# Layer1.net
KiCad netlist of a schematic drawn in EAGLE
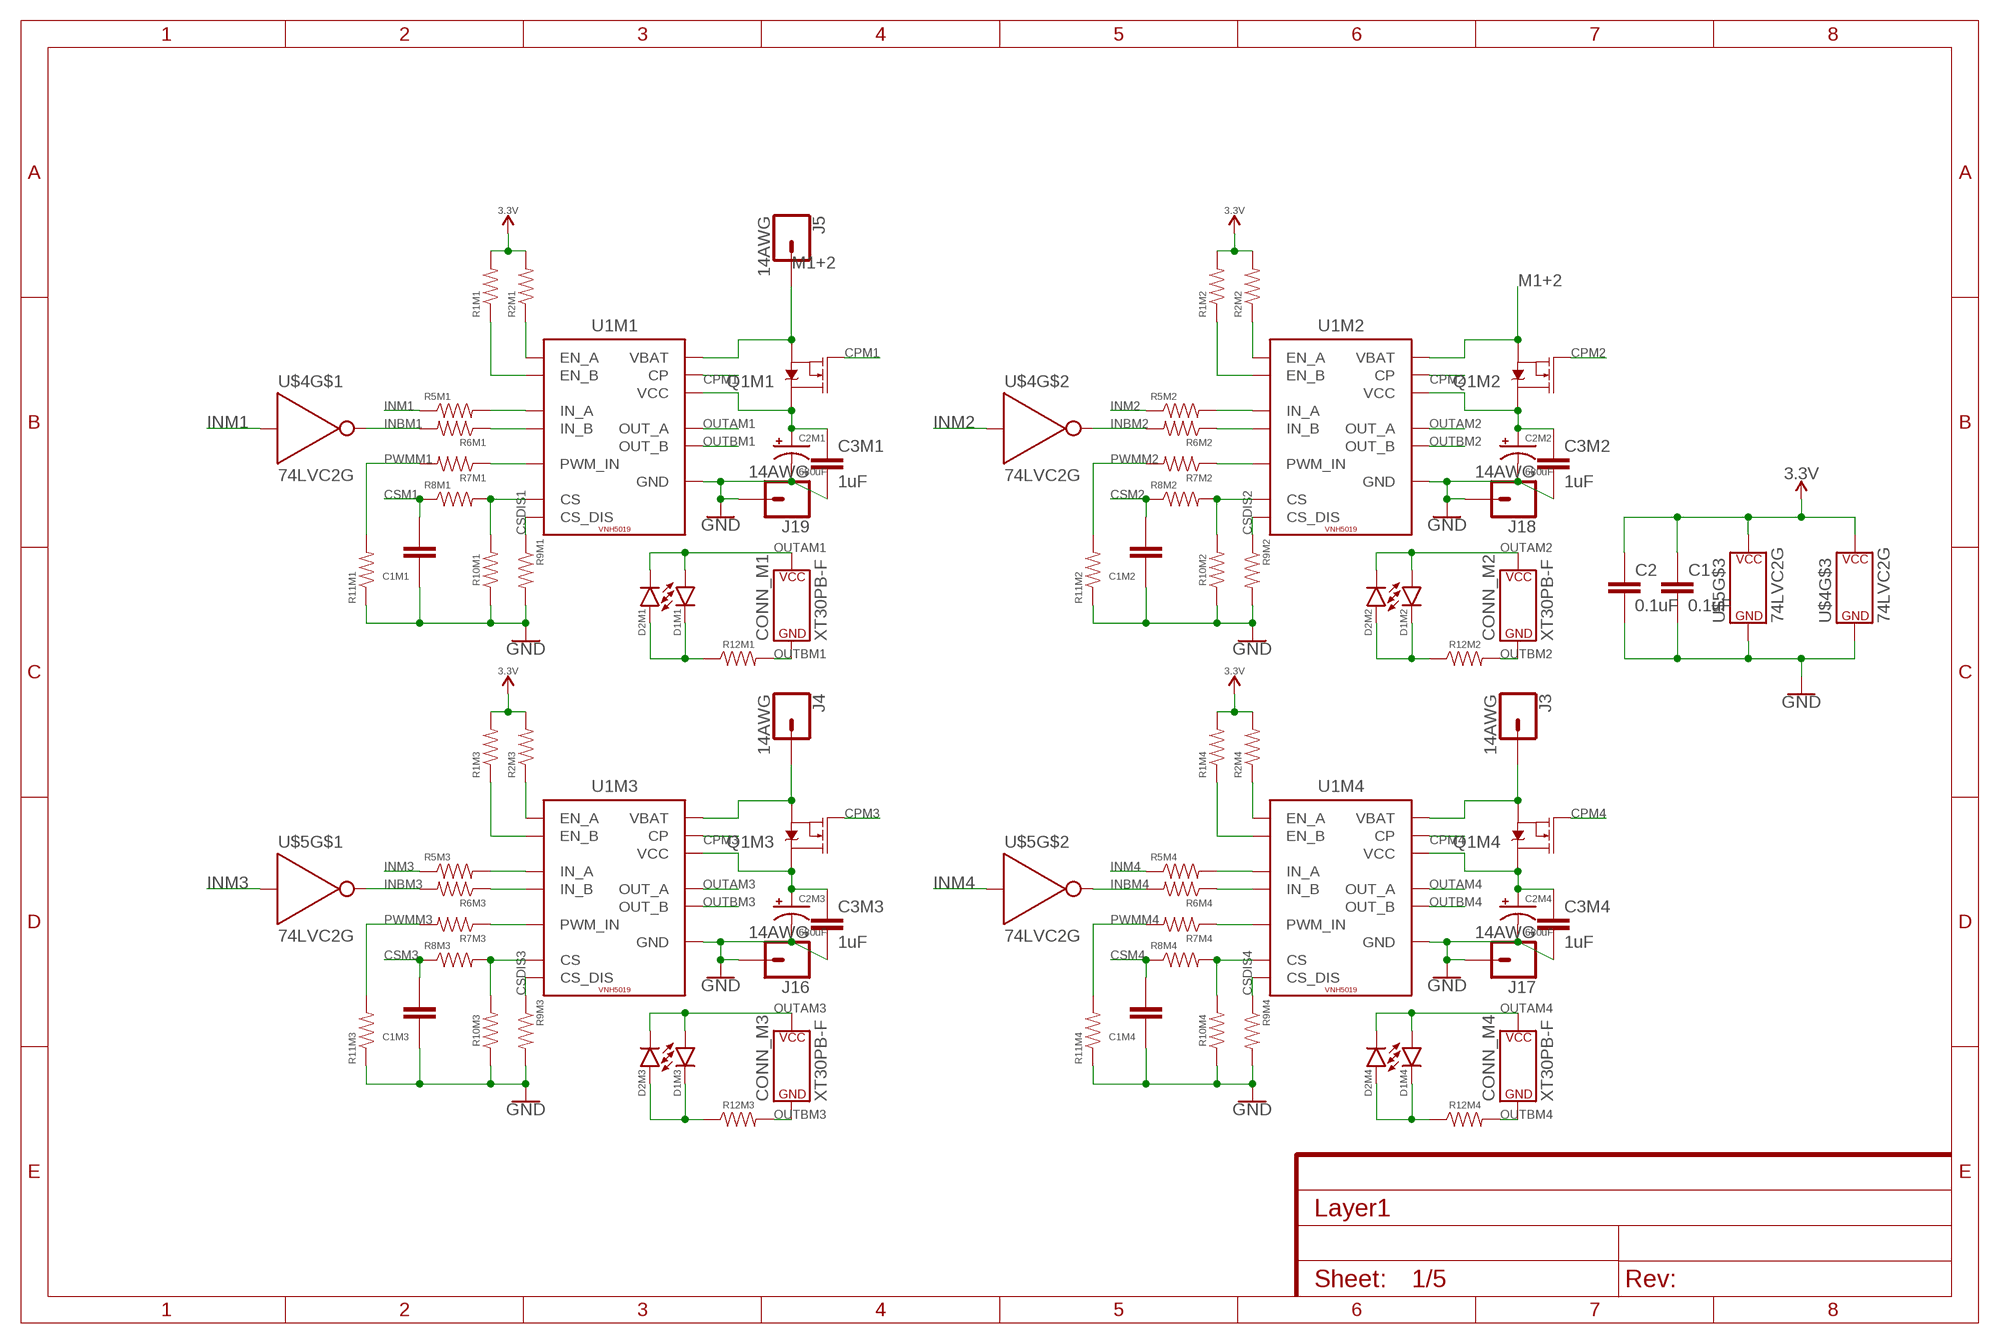
[diagram p0: schematic, sheet 1]
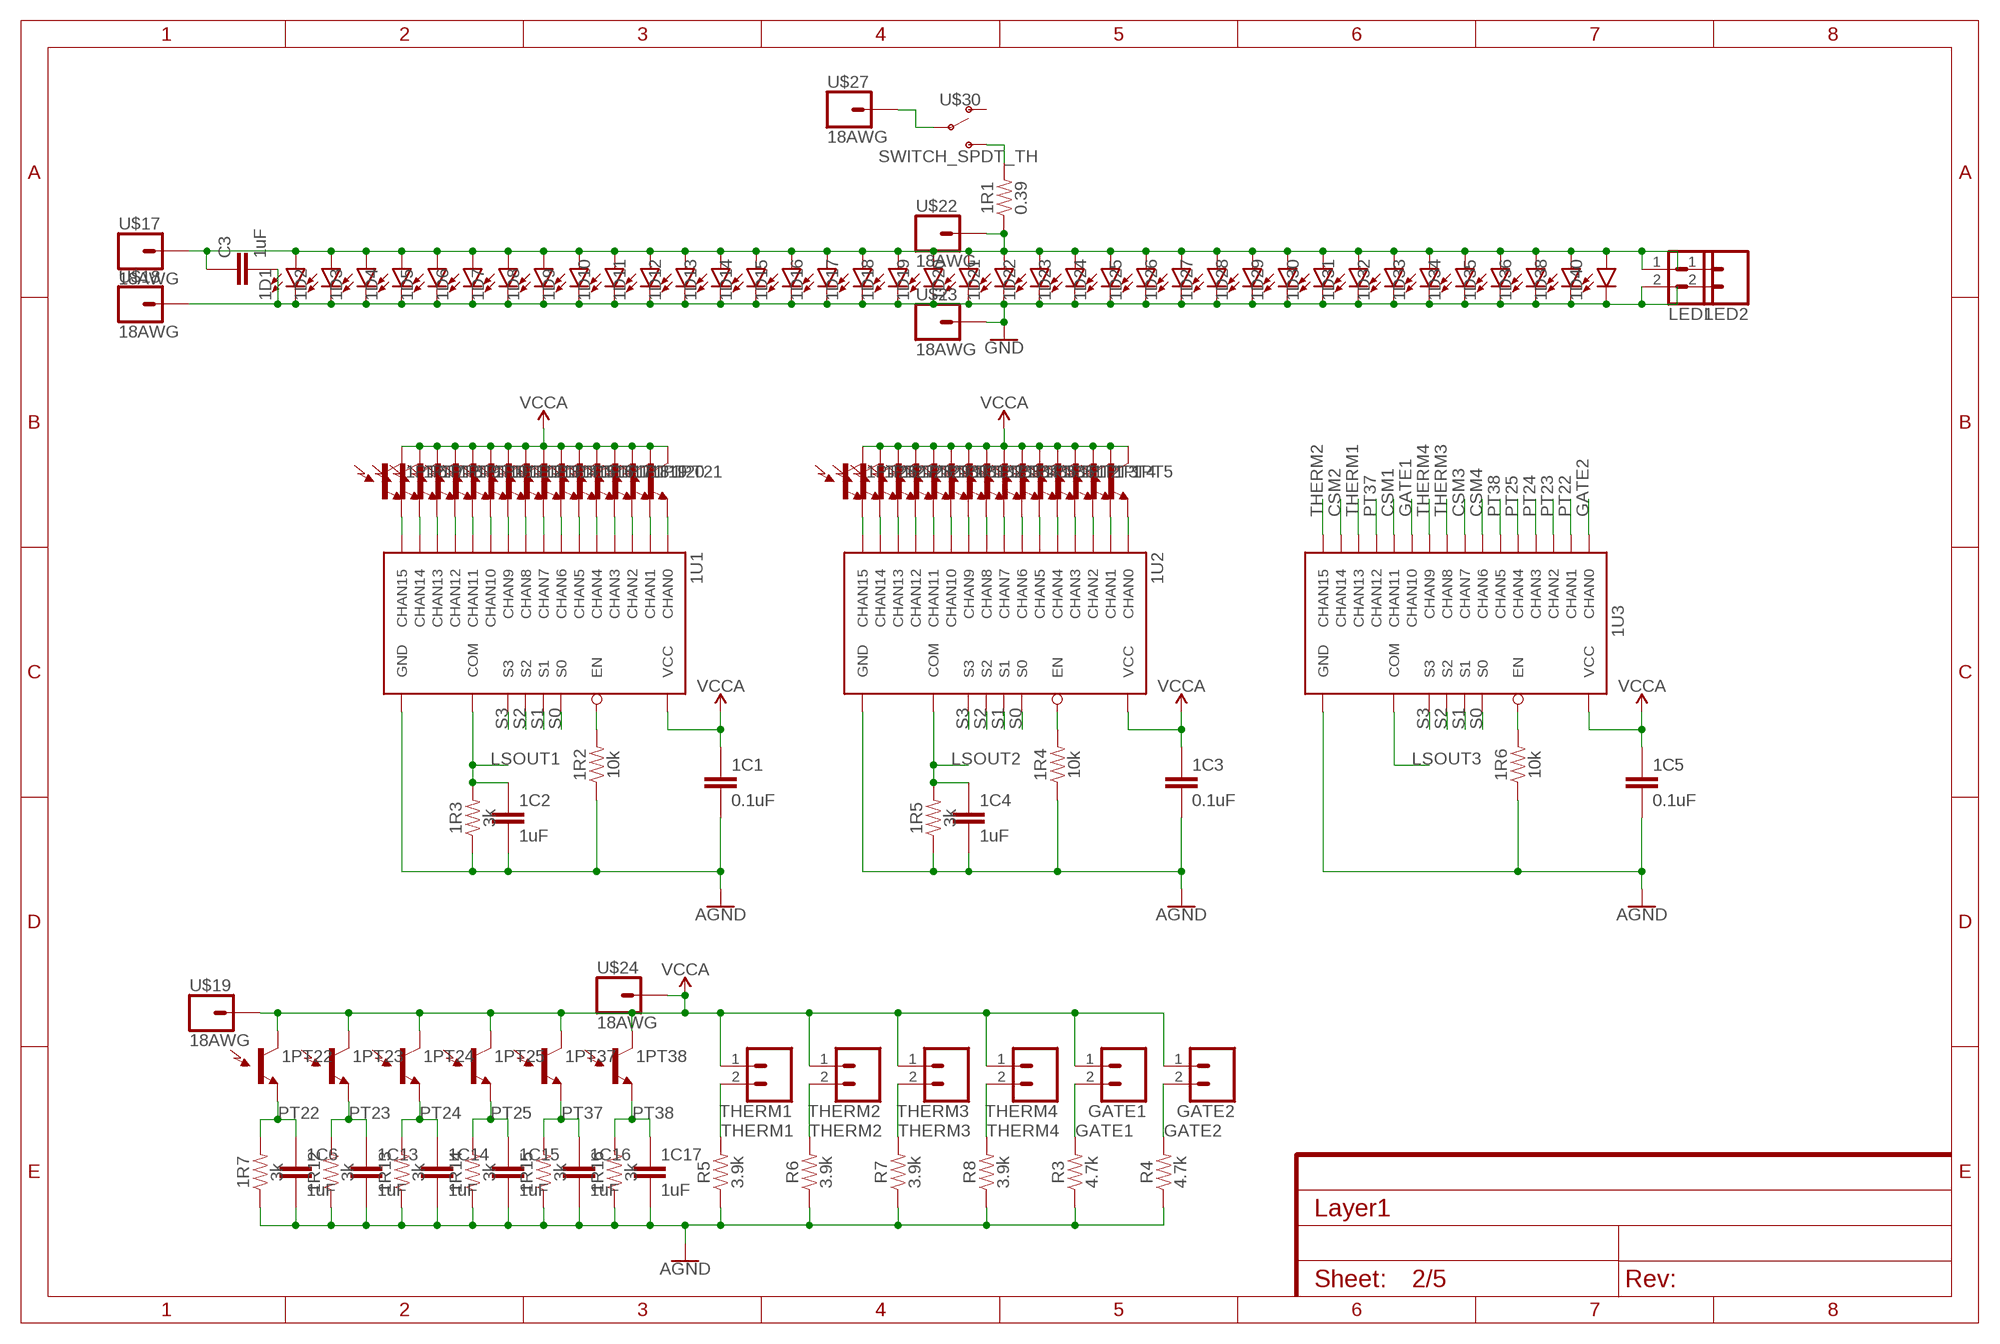
[diagram p1: schematic, sheet 2]
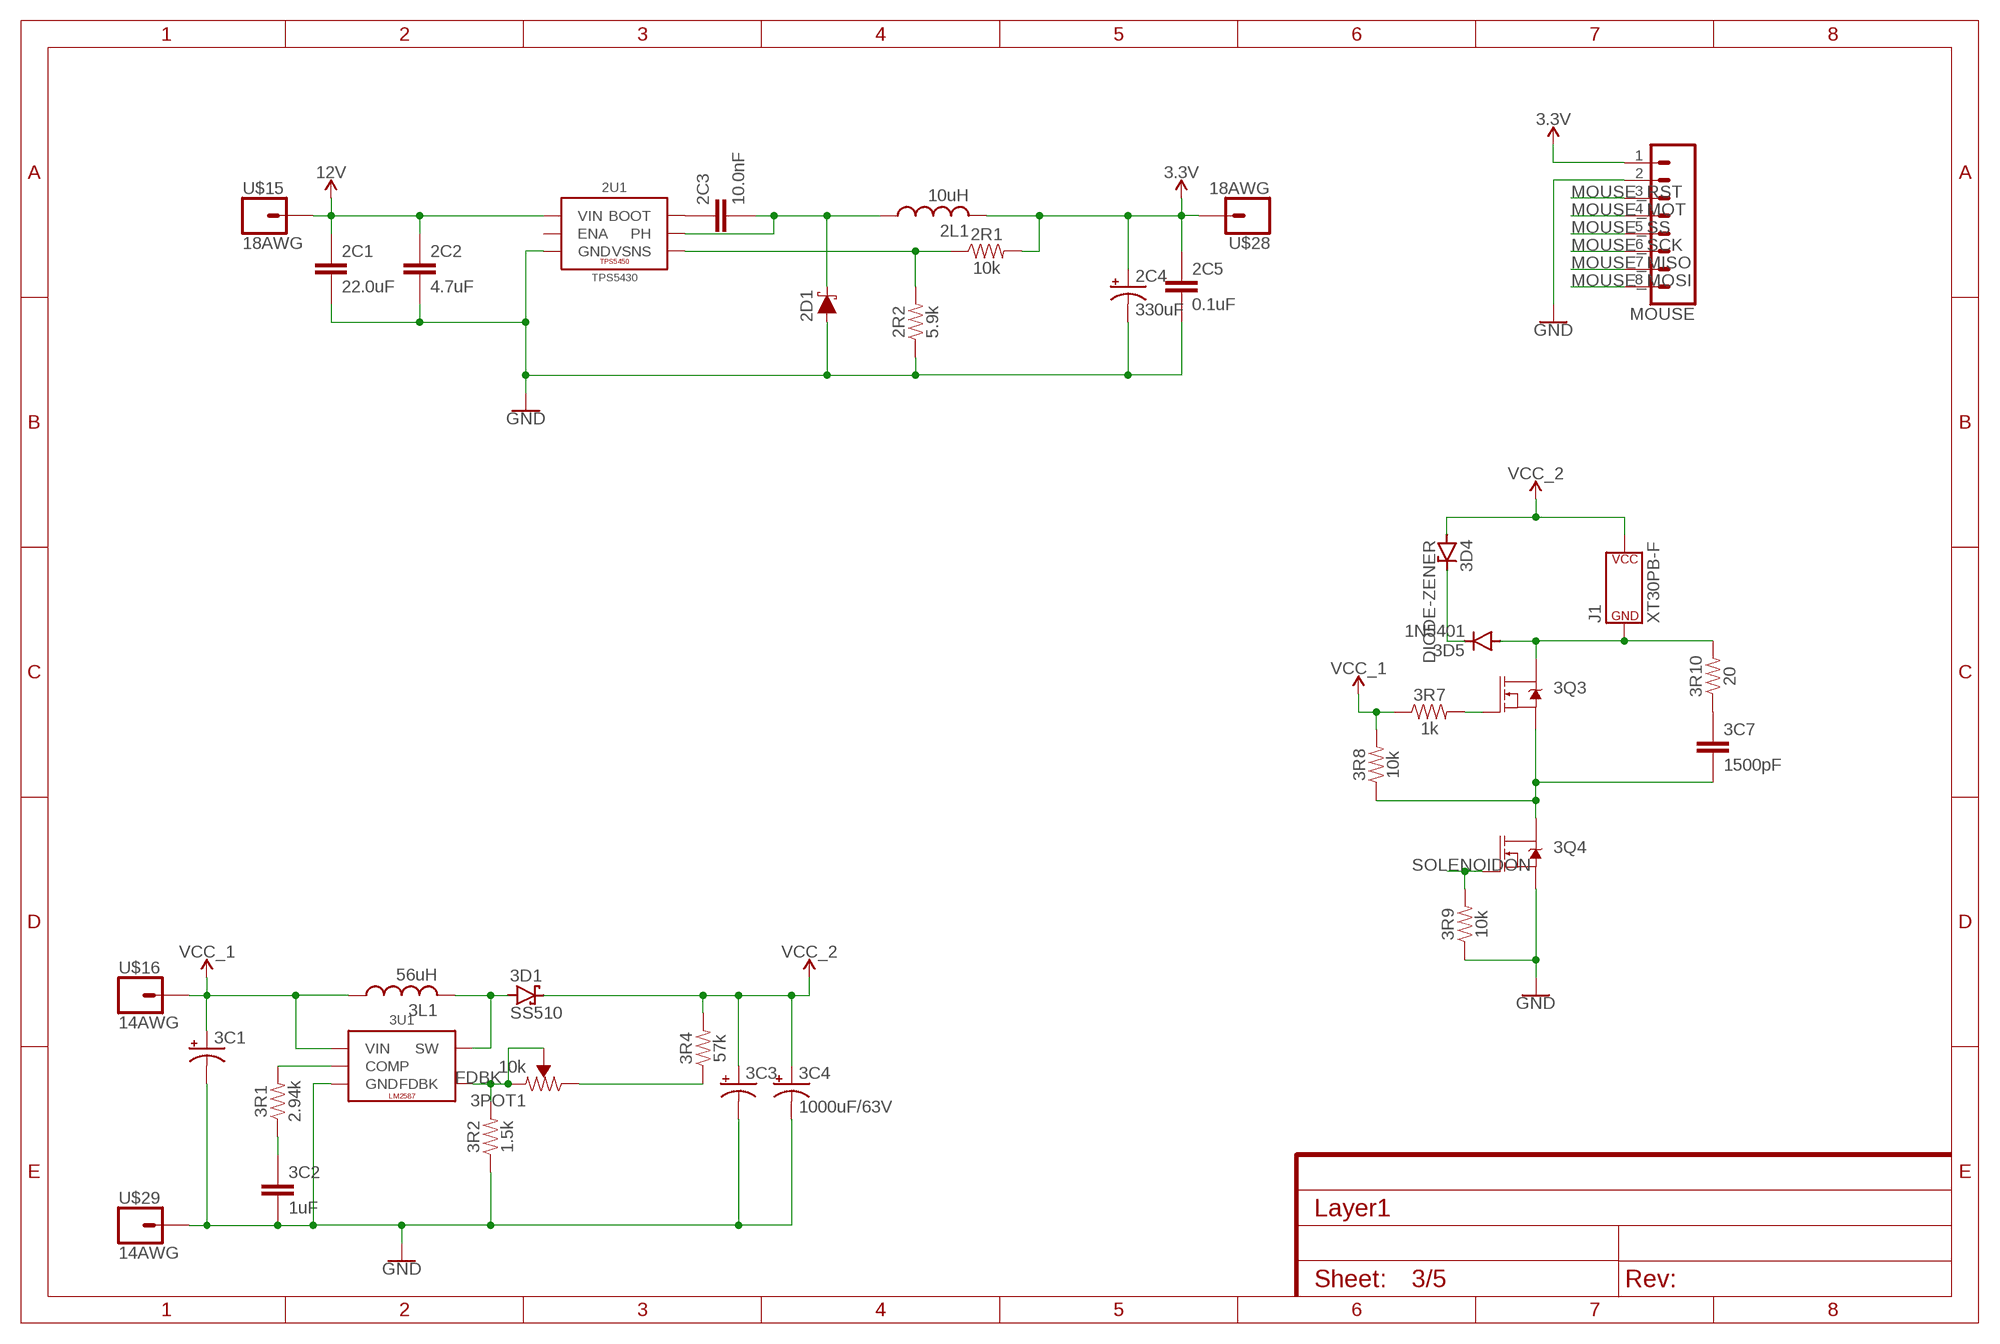
[diagram p2: schematic, sheet 3]
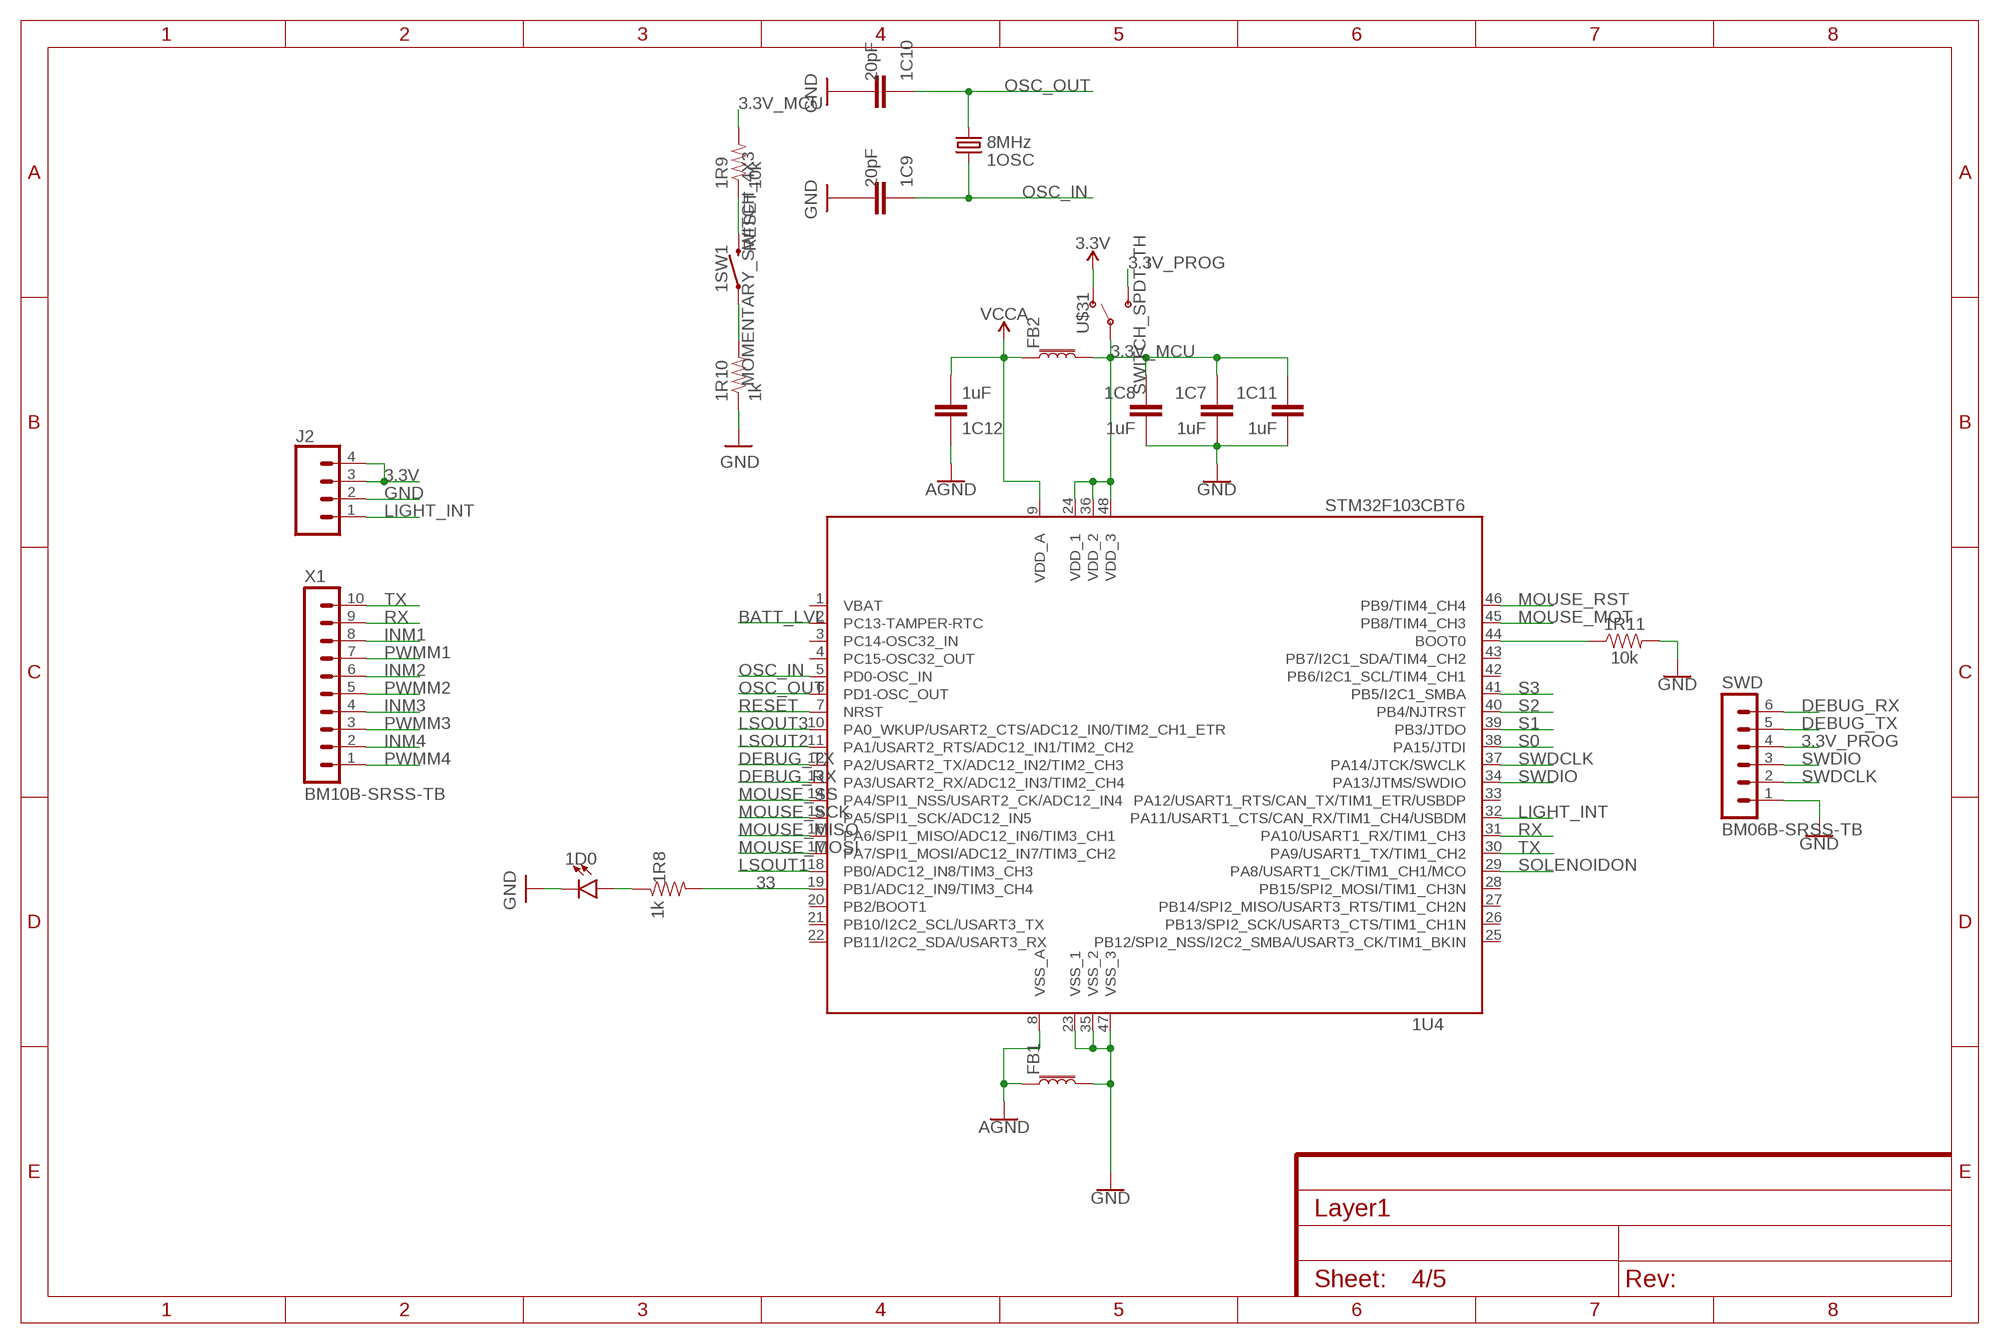
[diagram p3: schematic, sheet 4]
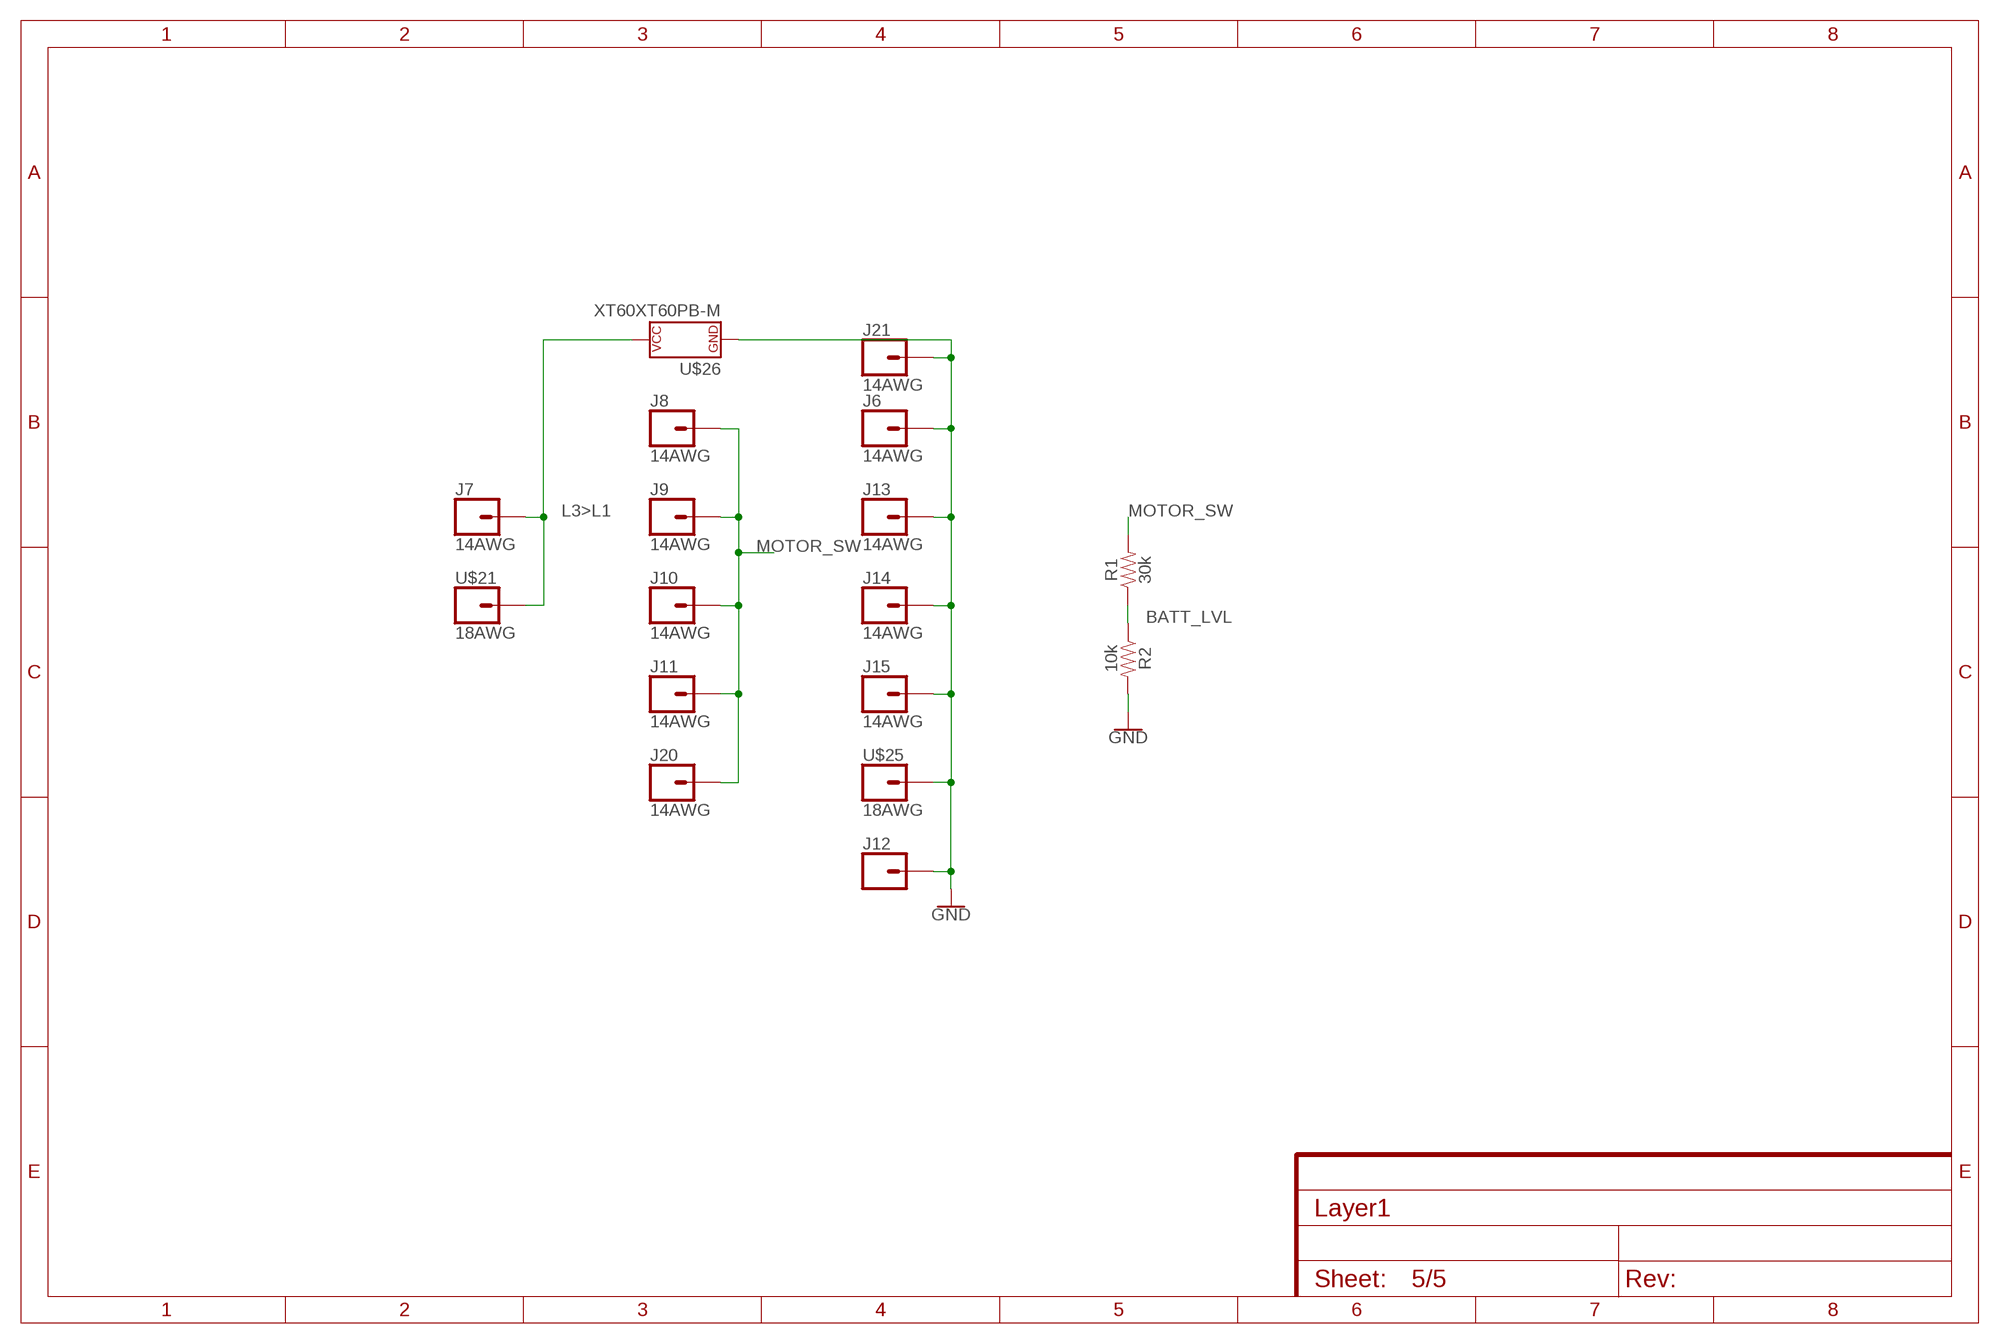
[diagram p4: schematic, sheet 5]

(export (version "E")
  (design (tool "Eeschema 10.0.6"))
  (components
    (comp (ref "J6")
      (value "14AWG")
      (footprint "eagle-import:14AWG")
      (libsource (lib "eagle-import") (part "14AWG"))
    )
    (comp (ref "J7")
      (value "14AWG")
      (footprint "eagle-import:14AWG")
      (libsource (lib "eagle-import") (part "14AWG"))
    )
    (comp (ref "J8")
      (value "14AWG")
      (footprint "eagle-import:14AWG")
      (libsource (lib "eagle-import") (part "14AWG"))
    )
    (comp (ref "J9")
      (value "14AWG")
      (footprint "eagle-import:14AWG")
      (libsource (lib "eagle-import") (part "14AWG"))
    )
    (comp (ref "J10")
      (value "14AWG")
      (footprint "eagle-import:14AWG")
      (libsource (lib "eagle-import") (part "14AWG"))
    )
    (comp (ref "J11")
      (value "14AWG")
      (footprint "eagle-import:14AWG")
      (libsource (lib "eagle-import") (part "14AWG"))
    )
    (comp (ref "J12")
      (value "CONN_01")
      (footprint "eagle-import:1X01")
      (libsource (lib "eagle-import") (part "CONN_01"))
    )
    (comp (ref "J13")
      (value "14AWG")
      (footprint "eagle-import:14AWG")
      (libsource (lib "eagle-import") (part "14AWG"))
    )
    (comp (ref "J14")
      (value "14AWG")
      (footprint "eagle-import:14AWG")
      (libsource (lib "eagle-import") (part "14AWG"))
    )
    (comp (ref "J15")
      (value "14AWG")
      (footprint "eagle-import:14AWG")
      (libsource (lib "eagle-import") (part "14AWG"))
    )
    (comp (ref "J20")
      (value "14AWG")
      (footprint "eagle-import:14AWG")
      (libsource (lib "eagle-import") (part "14AWG"))
    )
    (comp (ref "J21")
      (value "14AWG")
      (footprint "eagle-import:14AWG")
      (libsource (lib "eagle-import") (part "14AWG"))
    )
    (comp (ref "R1")
      (value "30k")
      (footprint "eagle-import:R0603")
      (libsource (lib "eagle-import") (part "RESISTOR0603"))
    )
    (comp (ref "R2")
      (value "10k")
      (footprint "eagle-import:R0603")
      (libsource (lib "eagle-import") (part "RESISTOR0603"))
    )
    (comp (ref "U$21")
      (value "18AWG")
      (footprint "eagle-import:18AWG")
      (libsource (lib "eagle-import") (part "18AWG"))
    )
    (comp (ref "U$25")
      (value "18AWG")
      (footprint "eagle-import:18AWG")
      (libsource (lib "eagle-import") (part "18AWG"))
    )
    (comp (ref "U$26")
      (value "XT60XT60PB-M")
      (footprint "eagle-import:XT60PB-M")
      (libsource (lib "eagle-import") (part "XT60XT60PB-M"))
    )
    (comp (ref "2C1")
      (value "22.0uF")
      (footprint "eagle-import:C1210")
      (libsource (lib "eagle-import") (part "CAPACITOR1210"))
    )
    (comp (ref "2C2")
      (value "4.7uF")
      (footprint "eagle-import:C0603")
      (libsource (lib "eagle-import") (part "CAPACITOR0603"))
    )
    (comp (ref "2C3")
      (value "10.0nF")
      (footprint "eagle-import:C0603")
      (libsource (lib "eagle-import") (part "CAPACITOR0603"))
    )
    (comp (ref "2C4")
      (value "330uF")
      (footprint "eagle-import:D_7343-31R")
      (libsource (lib "eagle-import") (part "CPOL-USD/7343-31R"))
    )
    (comp (ref "2C5")
      (value "0.1uF")
      (footprint "eagle-import:C0603")
      (libsource (lib "eagle-import") (part "CAPACITOR0603"))
    )
    (comp (ref "2D1")
      (value "SS54")
      (footprint "eagle-import:SMA-DIODE")
      (libsource (lib "eagle-import") (part "DIODE-SCHOTTKY"))
    )
    (comp (ref "2L1")
      (value "10uH")
      (footprint "eagle-import:SWPA8040")
      (libsource (lib "eagle-import") (part "INDUCTORSWPA8040"))
    )
    (comp (ref "2R1")
      (value "10k")
      (footprint "eagle-import:R0603")
      (libsource (lib "eagle-import") (part "RESISTOR0603"))
    )
    (comp (ref "2R2")
      (value "5.9k")
      (footprint "eagle-import:R0603")
      (libsource (lib "eagle-import") (part "RESISTOR0603"))
    )
    (comp (ref "2U1")
      (value "TPS5430")
      (footprint "eagle-import:POWERPAD-SOIC-8")
      (libsource (lib "eagle-import") (part "TPS5450"))
    )
    (comp (ref "3C1")
      (value "100uF")
      (footprint "eagle-import:PANASONIC_D")
      (libsource (lib "eagle-import") (part "CPOL-USD"))
    )
    (comp (ref "3C2")
      (value "1uF")
      (footprint "eagle-import:C0603")
      (libsource (lib "eagle-import") (part "CAPACITOR0603"))
    )
    (comp (ref "3C3")
      (value "CAPACITOR_POL_10X10.5MM")
      (footprint "eagle-import:10X10.5_CAP")
      (libsource (lib "eagle-import") (part "CAPACITOR_POL_10X10.5MM"))
    )
    (comp (ref "3C4")
      (value "1000uF/63V")
      (footprint "eagle-import:1000UF-CAP")
      (libsource (lib "eagle-import") (part "1000UF-CAP"))
    )
    (comp (ref "3C7")
      (value "1500pF")
      (footprint "eagle-import:C0603")
      (libsource (lib "eagle-import") (part "CAPACITOR0603"))
    )
    (comp (ref "3D1")
      (value "SS510")
      (footprint "eagle-import:SMB")
      (libsource (lib "eagle-import") (part "SCHOTTKY-DIODESMD"))
    )
    (comp (ref "3D4")
      (value "DIODE-ZENER")
      (footprint "eagle-import:DO41Z10")
      (libsource (lib "eagle-import") (part "DIODE-ZENER"))
    )
    (comp (ref "3D5")
      (value "1N5401")
      (footprint "eagle-import:DO201-15")
      (libsource (lib "eagle-import") (part "1N5400"))
    )
    (comp (ref "3L1")
      (value "56uH")
      (footprint "eagle-import:CDRH127")
      (libsource (lib "eagle-import") (part "INDUCTORCDRH127"))
    )
    (comp (ref "3POT1")
      (value "10k")
      (footprint "eagle-import:3296-TRIMPOT")
      (libsource (lib "eagle-import") (part "3296-TRIMPOT"))
    )
    (comp (ref "3Q3")
      (value "STP75NF75")
      (footprint "eagle-import:TO220V")
      (libsource (lib "eagle-import") (part "MOSFET-NCH-TO220V"))
    )
    (comp (ref "3Q4")
      (value "AO3400")
      (footprint "eagle-import:SOT23-3")
      (libsource (lib "eagle-import") (part "MOSFET-NCH-SOT23-3"))
    )
    (comp (ref "3R1")
      (value "2.94k")
      (footprint "eagle-import:R0603")
      (libsource (lib "eagle-import") (part "RESISTOR0603"))
    )
    (comp (ref "3R2")
      (value "1.5k")
      (footprint "eagle-import:R0603")
      (libsource (lib "eagle-import") (part "RESISTOR0603"))
    )
    (comp (ref "3R4")
      (value "57k")
      (footprint "eagle-import:R0603")
      (libsource (lib "eagle-import") (part "RESISTOR0603"))
    )
    (comp (ref "3R7")
      (value "1k")
      (footprint "eagle-import:R0603")
      (libsource (lib "eagle-import") (part "RESISTOR0603"))
    )
    (comp (ref "3R8")
      (value "10k")
      (footprint "eagle-import:R0603")
      (libsource (lib "eagle-import") (part "RESISTOR0603"))
    )
    (comp (ref "3R9")
      (value "10k")
      (footprint "eagle-import:R0603")
      (libsource (lib "eagle-import") (part "RESISTOR0603"))
    )
    (comp (ref "3R10")
      (value "20")
      (footprint "eagle-import:R0603")
      (libsource (lib "eagle-import") (part "RESISTOR0603"))
    )
    (comp (ref "3U1")
      (value "LM2587")
      (footprint "eagle-import:TO-263")
      (libsource (lib "eagle-import") (part "LM2587"))
    )
    (comp (ref "J1")
      (value "XT30PB-F")
      (footprint "eagle-import:XT30PB-F")
      (libsource (lib "eagle-import") (part "XT30PB-F"))
    )
    (comp (ref "MOUSE")
      (value "CONN_08LOCK")
      (footprint "eagle-import:1X08_LOCK")
      (libsource (lib "eagle-import") (part "CONN_08LOCK"))
    )
    (comp (ref "U$15")
      (value "18AWG")
      (footprint "eagle-import:18AWG")
      (libsource (lib "eagle-import") (part "18AWG"))
    )
    (comp (ref "U$16")
      (value "14AWG")
      (footprint "eagle-import:14AWG")
      (libsource (lib "eagle-import") (part "14AWG"))
    )
    (comp (ref "U$28")
      (value "18AWG")
      (footprint "eagle-import:18AWG")
      (libsource (lib "eagle-import") (part "18AWG"))
    )
    (comp (ref "U$29")
      (value "14AWG")
      (footprint "eagle-import:14AWG")
      (libsource (lib "eagle-import") (part "14AWG"))
    )
    (comp (ref "1C1")
      (value "0.1uF")
      (footprint "eagle-import:C0603")
      (libsource (lib "eagle-import") (part "CAPACITOR0603"))
    )
    (comp (ref "1C2")
      (value "1uF")
      (footprint "eagle-import:C0603")
      (libsource (lib "eagle-import") (part "CAPACITOR0603"))
    )
    (comp (ref "1C3")
      (value "0.1uF")
      (footprint "eagle-import:C0603")
      (libsource (lib "eagle-import") (part "CAPACITOR0603"))
    )
    (comp (ref "1C4")
      (value "1uF")
      (footprint "eagle-import:C0603")
      (libsource (lib "eagle-import") (part "CAPACITOR0603"))
    )
    (comp (ref "1C5")
      (value "0.1uF")
      (footprint "eagle-import:C0603")
      (libsource (lib "eagle-import") (part "CAPACITOR0603"))
    )
    (comp (ref "1C6")
      (value "1uF")
      (footprint "eagle-import:C0603")
      (libsource (lib "eagle-import") (part "CAPACITOR0603"))
    )
    (comp (ref "1C13")
      (value "1uF")
      (footprint "eagle-import:C0603")
      (libsource (lib "eagle-import") (part "CAPACITOR0603"))
    )
    (comp (ref "1C14")
      (value "1uF")
      (footprint "eagle-import:C0603")
      (libsource (lib "eagle-import") (part "CAPACITOR0603"))
    )
    (comp (ref "1C15")
      (value "1uF")
      (footprint "eagle-import:C0603")
      (libsource (lib "eagle-import") (part "CAPACITOR0603"))
    )
    (comp (ref "1C16")
      (value "1uF")
      (footprint "eagle-import:C0603")
      (libsource (lib "eagle-import") (part "CAPACITOR0603"))
    )
    (comp (ref "1C17")
      (value "1uF")
      (footprint "eagle-import:C0603")
      (libsource (lib "eagle-import") (part "CAPACITOR0603"))
    )
    (comp (ref "1D1")
      (value "3528LED")
      (footprint "eagle-import:3528")
      (libsource (lib "eagle-import") (part "3528LED"))
    )
    (comp (ref "1D2")
      (value "3528LED")
      (footprint "eagle-import:3528")
      (libsource (lib "eagle-import") (part "3528LED"))
    )
    (comp (ref "1D3")
      (value "3528LED")
      (footprint "eagle-import:3528")
      (libsource (lib "eagle-import") (part "3528LED"))
    )
    (comp (ref "1D4")
      (value "3528LED")
      (footprint "eagle-import:3528")
      (libsource (lib "eagle-import") (part "3528LED"))
    )
    (comp (ref "1D5")
      (value "3528LED")
      (footprint "eagle-import:3528")
      (libsource (lib "eagle-import") (part "3528LED"))
    )
    (comp (ref "1D6")
      (value "3528LED")
      (footprint "eagle-import:3528")
      (libsource (lib "eagle-import") (part "3528LED"))
    )
    (comp (ref "1D7")
      (value "3528LED")
      (footprint "eagle-import:3528")
      (libsource (lib "eagle-import") (part "3528LED"))
    )
    (comp (ref "1D8")
      (value "3528LED")
      (footprint "eagle-import:3528")
      (libsource (lib "eagle-import") (part "3528LED"))
    )
    (comp (ref "1D9")
      (value "3528LED")
      (footprint "eagle-import:3528")
      (libsource (lib "eagle-import") (part "3528LED"))
    )
    (comp (ref "1D10")
      (value "3528LED")
      (footprint "eagle-import:3528")
      (libsource (lib "eagle-import") (part "3528LED"))
    )
    (comp (ref "1D11")
      (value "3528LED")
      (footprint "eagle-import:3528")
      (libsource (lib "eagle-import") (part "3528LED"))
    )
    (comp (ref "1D12")
      (value "3528LED")
      (footprint "eagle-import:3528")
      (libsource (lib "eagle-import") (part "3528LED"))
    )
    (comp (ref "1D13")
      (value "3528LED")
      (footprint "eagle-import:3528")
      (libsource (lib "eagle-import") (part "3528LED"))
    )
    (comp (ref "1D14")
      (value "3528LED")
      (footprint "eagle-import:3528")
      (libsource (lib "eagle-import") (part "3528LED"))
    )
    (comp (ref "1D15")
      (value "3528LED")
      (footprint "eagle-import:3528")
      (libsource (lib "eagle-import") (part "3528LED"))
    )
    (comp (ref "1D16")
      (value "3528LED")
      (footprint "eagle-import:3528")
      (libsource (lib "eagle-import") (part "3528LED"))
    )
    (comp (ref "1D17")
      (value "3528LED")
      (footprint "eagle-import:3528")
      (libsource (lib "eagle-import") (part "3528LED"))
    )
    (comp (ref "1D18")
      (value "3528LED")
      (footprint "eagle-import:3528")
      (libsource (lib "eagle-import") (part "3528LED"))
    )
    (comp (ref "1D19")
      (value "3528LED")
      (footprint "eagle-import:3528")
      (libsource (lib "eagle-import") (part "3528LED"))
    )
    (comp (ref "1D20")
      (value "3528LED")
      (footprint "eagle-import:3528")
      (libsource (lib "eagle-import") (part "3528LED"))
    )
    (comp (ref "1D21")
      (value "3528LED")
      (footprint "eagle-import:3528")
      (libsource (lib "eagle-import") (part "3528LED"))
    )
    (comp (ref "1D22")
      (value "3528LED")
      (footprint "eagle-import:3528")
      (libsource (lib "eagle-import") (part "3528LED"))
    )
    (comp (ref "1D23")
      (value "3528LED")
      (footprint "eagle-import:3528")
      (libsource (lib "eagle-import") (part "3528LED"))
    )
    (comp (ref "1D24")
      (value "3528LED")
      (footprint "eagle-import:3528")
      (libsource (lib "eagle-import") (part "3528LED"))
    )
    (comp (ref "1D25")
      (value "3528LED")
      (footprint "eagle-import:3528")
      (libsource (lib "eagle-import") (part "3528LED"))
    )
    (comp (ref "1D26")
      (value "3528LED")
      (footprint "eagle-import:3528")
      (libsource (lib "eagle-import") (part "3528LED"))
    )
    (comp (ref "1D27")
      (value "3528LED")
      (footprint "eagle-import:3528")
      (libsource (lib "eagle-import") (part "3528LED"))
    )
    (comp (ref "1D28")
      (value "3528LED")
      (footprint "eagle-import:3528")
      (libsource (lib "eagle-import") (part "3528LED"))
    )
    (comp (ref "1D29")
      (value "3528LED")
      (footprint "eagle-import:3528")
      (libsource (lib "eagle-import") (part "3528LED"))
    )
    (comp (ref "1D30")
      (value "3528LED")
      (footprint "eagle-import:3528")
      (libsource (lib "eagle-import") (part "3528LED"))
    )
    (comp (ref "1D31")
      (value "3528LED")
      (footprint "eagle-import:3528")
      (libsource (lib "eagle-import") (part "3528LED"))
    )
    (comp (ref "1D32")
      (value "3528LED")
      (footprint "eagle-import:3528")
      (libsource (lib "eagle-import") (part "3528LED"))
    )
    (comp (ref "1D33")
      (value "3528LED")
      (footprint "eagle-import:3528")
      (libsource (lib "eagle-import") (part "3528LED"))
    )
    (comp (ref "1D34")
      (value "3528LED")
      (footprint "eagle-import:3528")
      (libsource (lib "eagle-import") (part "3528LED"))
    )
    (comp (ref "1D35")
      (value "3528LED")
      (footprint "eagle-import:3528")
      (libsource (lib "eagle-import") (part "3528LED"))
    )
    (comp (ref "1D36")
      (value "3528LED")
      (footprint "eagle-import:3528")
      (libsource (lib "eagle-import") (part "3528LED"))
    )
    (comp (ref "1D38")
      (value "3528LED")
      (footprint "eagle-import:3528")
      (libsource (lib "eagle-import") (part "3528LED"))
    )
    (comp (ref "1D40")
      (value "3528LED")
      (footprint "eagle-import:3528")
      (libsource (lib "eagle-import") (part "3528LED"))
    )
    (comp (ref "1PT1")
      (value "LIGHT_SENSOR_ALS")
      (footprint "eagle-import:ALS-PT19")
      (libsource (lib "eagle-import") (part "LIGHT_SENSOR_ALS"))
    )
    (comp (ref "1PT2")
      (value "LIGHT_SENSOR_ALS")
      (footprint "eagle-import:ALS-PT19")
      (libsource (lib "eagle-import") (part "LIGHT_SENSOR_ALS"))
    )
    (comp (ref "1PT3")
      (value "LIGHT_SENSOR_ALS")
      (footprint "eagle-import:ALS-PT19")
      (libsource (lib "eagle-import") (part "LIGHT_SENSOR_ALS"))
    )
    (comp (ref "1PT4")
      (value "LIGHT_SENSOR_ALS")
      (footprint "eagle-import:ALS-PT19")
      (libsource (lib "eagle-import") (part "LIGHT_SENSOR_ALS"))
    )
    (comp (ref "1PT5")
      (value "LIGHT_SENSOR_ALS")
      (footprint "eagle-import:ALS-PT19")
      (libsource (lib "eagle-import") (part "LIGHT_SENSOR_ALS"))
    )
    (comp (ref "1PT6")
      (value "LIGHT_SENSOR_ALS")
      (footprint "eagle-import:ALS-PT19")
      (libsource (lib "eagle-import") (part "LIGHT_SENSOR_ALS"))
    )
    (comp (ref "1PT7")
      (value "LIGHT_SENSOR_ALS")
      (footprint "eagle-import:ALS-PT19")
      (libsource (lib "eagle-import") (part "LIGHT_SENSOR_ALS"))
    )
    (comp (ref "1PT8")
      (value "LIGHT_SENSOR_ALS")
      (footprint "eagle-import:ALS-PT19")
      (libsource (lib "eagle-import") (part "LIGHT_SENSOR_ALS"))
    )
    (comp (ref "1PT9")
      (value "LIGHT_SENSOR_ALS")
      (footprint "eagle-import:ALS-PT19")
      (libsource (lib "eagle-import") (part "LIGHT_SENSOR_ALS"))
    )
    (comp (ref "1PT10")
      (value "LIGHT_SENSOR_ALS")
      (footprint "eagle-import:ALS-PT19")
      (libsource (lib "eagle-import") (part "LIGHT_SENSOR_ALS"))
    )
    (comp (ref "1PT11")
      (value "LIGHT_SENSOR_ALS")
      (footprint "eagle-import:ALS-PT19")
      (libsource (lib "eagle-import") (part "LIGHT_SENSOR_ALS"))
    )
    (comp (ref "1PT12")
      (value "LIGHT_SENSOR_ALS")
      (footprint "eagle-import:ALS-PT19")
      (libsource (lib "eagle-import") (part "LIGHT_SENSOR_ALS"))
    )
    (comp (ref "1PT13")
      (value "LIGHT_SENSOR_ALS")
      (footprint "eagle-import:ALS-PT19")
      (libsource (lib "eagle-import") (part "LIGHT_SENSOR_ALS"))
    )
    (comp (ref "1PT14")
      (value "LIGHT_SENSOR_ALS")
      (footprint "eagle-import:ALS-PT19")
      (libsource (lib "eagle-import") (part "LIGHT_SENSOR_ALS"))
    )
    (comp (ref "1PT15")
      (value "LIGHT_SENSOR_ALS")
      (footprint "eagle-import:ALS-PT19")
      (libsource (lib "eagle-import") (part "LIGHT_SENSOR_ALS"))
    )
    (comp (ref "1PT16")
      (value "LIGHT_SENSOR_ALS")
      (footprint "eagle-import:ALS-PT19")
      (libsource (lib "eagle-import") (part "LIGHT_SENSOR_ALS"))
    )
    (comp (ref "1PT17")
      (value "LIGHT_SENSOR_ALS")
      (footprint "eagle-import:ALS-PT19")
      (libsource (lib "eagle-import") (part "LIGHT_SENSOR_ALS"))
    )
    (comp (ref "1PT18")
      (value "LIGHT_SENSOR_ALS")
      (footprint "eagle-import:ALS-PT19")
      (libsource (lib "eagle-import") (part "LIGHT_SENSOR_ALS"))
    )
    (comp (ref "1PT19")
      (value "LIGHT_SENSOR_ALS")
      (footprint "eagle-import:ALS-PT19")
      (libsource (lib "eagle-import") (part "LIGHT_SENSOR_ALS"))
    )
    (comp (ref "1PT20")
      (value "LIGHT_SENSOR_ALS")
      (footprint "eagle-import:ALS-PT19")
      (libsource (lib "eagle-import") (part "LIGHT_SENSOR_ALS"))
    )
    (comp (ref "1PT21")
      (value "LIGHT_SENSOR_ALS")
      (footprint "eagle-import:ALS-PT19")
      (libsource (lib "eagle-import") (part "LIGHT_SENSOR_ALS"))
    )
    (comp (ref "1PT22")
      (value "LIGHT_SENSOR_ALS")
      (footprint "eagle-import:ALS-PT19")
      (libsource (lib "eagle-import") (part "LIGHT_SENSOR_ALS"))
    )
    (comp (ref "1PT23")
      (value "LIGHT_SENSOR_ALS")
      (footprint "eagle-import:ALS-PT19")
      (libsource (lib "eagle-import") (part "LIGHT_SENSOR_ALS"))
    )
    (comp (ref "1PT24")
      (value "LIGHT_SENSOR_ALS")
      (footprint "eagle-import:ALS-PT19")
      (libsource (lib "eagle-import") (part "LIGHT_SENSOR_ALS"))
    )
    (comp (ref "1PT25")
      (value "LIGHT_SENSOR_ALS")
      (footprint "eagle-import:ALS-PT19")
      (libsource (lib "eagle-import") (part "LIGHT_SENSOR_ALS"))
    )
    (comp (ref "1PT26")
      (value "LIGHT_SENSOR_ALS")
      (footprint "eagle-import:ALS-PT19")
      (libsource (lib "eagle-import") (part "LIGHT_SENSOR_ALS"))
    )
    (comp (ref "1PT27")
      (value "LIGHT_SENSOR_ALS")
      (footprint "eagle-import:ALS-PT19")
      (libsource (lib "eagle-import") (part "LIGHT_SENSOR_ALS"))
    )
    (comp (ref "1PT28")
      (value "LIGHT_SENSOR_ALS")
      (footprint "eagle-import:ALS-PT19")
      (libsource (lib "eagle-import") (part "LIGHT_SENSOR_ALS"))
    )
    (comp (ref "1PT29")
      (value "LIGHT_SENSOR_ALS")
      (footprint "eagle-import:ALS-PT19")
      (libsource (lib "eagle-import") (part "LIGHT_SENSOR_ALS"))
    )
    (comp (ref "1PT30")
      (value "LIGHT_SENSOR_ALS")
      (footprint "eagle-import:ALS-PT19")
      (libsource (lib "eagle-import") (part "LIGHT_SENSOR_ALS"))
    )
    (comp (ref "1PT31")
      (value "LIGHT_SENSOR_ALS")
      (footprint "eagle-import:ALS-PT19")
      (libsource (lib "eagle-import") (part "LIGHT_SENSOR_ALS"))
    )
    (comp (ref "1PT32")
      (value "LIGHT_SENSOR_ALS")
      (footprint "eagle-import:ALS-PT19")
      (libsource (lib "eagle-import") (part "LIGHT_SENSOR_ALS"))
    )
    (comp (ref "1PT33")
      (value "LIGHT_SENSOR_ALS")
      (footprint "eagle-import:ALS-PT19")
      (libsource (lib "eagle-import") (part "LIGHT_SENSOR_ALS"))
    )
    (comp (ref "1PT34")
      (value "LIGHT_SENSOR_ALS")
      (footprint "eagle-import:ALS-PT19")
      (libsource (lib "eagle-import") (part "LIGHT_SENSOR_ALS"))
    )
    (comp (ref "1PT35")
      (value "LIGHT_SENSOR_ALS")
      (footprint "eagle-import:ALS-PT19")
      (libsource (lib "eagle-import") (part "LIGHT_SENSOR_ALS"))
    )
    (comp (ref "1PT36")
      (value "LIGHT_SENSOR_ALS")
      (footprint "eagle-import:ALS-PT19")
      (libsource (lib "eagle-import") (part "LIGHT_SENSOR_ALS"))
    )
    (comp (ref "1PT37")
      (value "LIGHT_SENSOR_ALS")
      (footprint "eagle-import:ALS-PT19")
      (libsource (lib "eagle-import") (part "LIGHT_SENSOR_ALS"))
    )
    (comp (ref "1PT38")
      (value "LIGHT_SENSOR_ALS")
      (footprint "eagle-import:ALS-PT19")
      (libsource (lib "eagle-import") (part "LIGHT_SENSOR_ALS"))
    )
    (comp (ref "1R1")
      (value "0.39")
      (footprint "eagle-import:R0603")
      (libsource (lib "eagle-import") (part "RESISTOR0603"))
    )
    (comp (ref "1R2")
      (value "10k")
      (footprint "eagle-import:R0603")
      (libsource (lib "eagle-import") (part "RESISTOR0603"))
    )
    (comp (ref "1R3")
      (value "3k")
      (footprint "eagle-import:R0603")
      (libsource (lib "eagle-import") (part "RESISTOR0603"))
    )
    (comp (ref "1R4")
      (value "10k")
      (footprint "eagle-import:R0603")
      (libsource (lib "eagle-import") (part "RESISTOR0603"))
    )
    (comp (ref "1R5")
      (value "3k")
      (footprint "eagle-import:R0603")
      (libsource (lib "eagle-import") (part "RESISTOR0603"))
    )
    (comp (ref "1R6")
      (value "10k")
      (footprint "eagle-import:R0603")
      (libsource (lib "eagle-import") (part "RESISTOR0603"))
    )
    (comp (ref "1R7")
      (value "3k")
      (footprint "eagle-import:R0603")
      (libsource (lib "eagle-import") (part "RESISTOR0603"))
    )
    (comp (ref "1R12")
      (value "3k")
      (footprint "eagle-import:R0603")
      (libsource (lib "eagle-import") (part "RESISTOR0603"))
    )
    (comp (ref "1R13")
      (value "3k")
      (footprint "eagle-import:R0603")
      (libsource (lib "eagle-import") (part "RESISTOR0603"))
    )
    (comp (ref "1R14")
      (value "3k")
      (footprint "eagle-import:R0603")
      (libsource (lib "eagle-import") (part "RESISTOR0603"))
    )
    (comp (ref "1R15")
      (value "3k")
      (footprint "eagle-import:R0603")
      (libsource (lib "eagle-import") (part "RESISTOR0603"))
    )
    (comp (ref "1R16")
      (value "3k")
      (footprint "eagle-import:R0603")
      (libsource (lib "eagle-import") (part "RESISTOR0603"))
    )
    (comp (ref "1U1")
      (value "CD74HC4067SSOP-24")
      (footprint "eagle-import:SSOP24")
      (libsource (lib "eagle-import") (part "CD74HC4067SSOP-24"))
    )
    (comp (ref "1U2")
      (value "CD74HC4067SSOP-24")
      (footprint "eagle-import:SSOP24")
      (libsource (lib "eagle-import") (part "CD74HC4067SSOP-24"))
    )
    (comp (ref "1U3")
      (value "CD74HC4067SSOP-24")
      (footprint "eagle-import:SSOP24")
      (libsource (lib "eagle-import") (part "CD74HC4067SSOP-24"))
    )
    (comp (ref "C3")
      (value "1uF")
      (footprint "eagle-import:C0603")
      (libsource (lib "eagle-import") (part "CAPACITOR0603"))
    )
    (comp (ref "GATE1")
      (value "CONN_021X02_NO_SILK")
      (footprint "eagle-import:1X02_NO_SILK")
      (libsource (lib "eagle-import") (part "CONN_021X02_NO_SILK"))
    )
    (comp (ref "GATE2")
      (value "CONN_021X02_NO_SILK")
      (footprint "eagle-import:1X02_NO_SILK")
      (libsource (lib "eagle-import") (part "CONN_021X02_NO_SILK"))
    )
    (comp (ref "LED1")
      (value "CONN_021X02_NO_SILK")
      (footprint "eagle-import:1X02_NO_SILK")
      (libsource (lib "eagle-import") (part "CONN_021X02_NO_SILK"))
    )
    (comp (ref "LED2")
      (value "CONN_021X02_NO_SILK")
      (footprint "eagle-import:1X02_NO_SILK")
      (libsource (lib "eagle-import") (part "CONN_021X02_NO_SILK"))
    )
    (comp (ref "R3")
      (value "4.7k")
      (footprint "eagle-import:R0603")
      (libsource (lib "eagle-import") (part "RESISTOR0603"))
    )
    (comp (ref "R4")
      (value "4.7k")
      (footprint "eagle-import:R0603")
      (libsource (lib "eagle-import") (part "RESISTOR0603"))
    )
    (comp (ref "R5")
      (value "3.9k")
      (footprint "eagle-import:R0603")
      (libsource (lib "eagle-import") (part "RESISTOR0603"))
    )
    (comp (ref "R6")
      (value "3.9k")
      (footprint "eagle-import:R0603")
      (libsource (lib "eagle-import") (part "RESISTOR0603"))
    )
    (comp (ref "R7")
      (value "3.9k")
      (footprint "eagle-import:R0603")
      (libsource (lib "eagle-import") (part "RESISTOR0603"))
    )
    (comp (ref "R8")
      (value "3.9k")
      (footprint "eagle-import:R0603")
      (libsource (lib "eagle-import") (part "RESISTOR0603"))
    )
    (comp (ref "THERM1")
      (value "CONN_021X02_NO_SILK")
      (footprint "eagle-import:1X02_NO_SILK")
      (libsource (lib "eagle-import") (part "CONN_021X02_NO_SILK"))
    )
    (comp (ref "THERM2")
      (value "CONN_021X02_NO_SILK")
      (footprint "eagle-import:1X02_NO_SILK")
      (libsource (lib "eagle-import") (part "CONN_021X02_NO_SILK"))
    )
    (comp (ref "THERM3")
      (value "CONN_021X02_NO_SILK")
      (footprint "eagle-import:1X02_NO_SILK")
      (libsource (lib "eagle-import") (part "CONN_021X02_NO_SILK"))
    )
    (comp (ref "THERM4")
      (value "CONN_021X02_NO_SILK")
      (footprint "eagle-import:1X02_NO_SILK")
      (libsource (lib "eagle-import") (part "CONN_021X02_NO_SILK"))
    )
    (comp (ref "U$17")
      (value "18AWG")
      (footprint "eagle-import:18AWG")
      (libsource (lib "eagle-import") (part "18AWG"))
    )
    (comp (ref "U$18")
      (value "18AWG")
      (footprint "eagle-import:18AWG")
      (libsource (lib "eagle-import") (part "18AWG"))
    )
    (comp (ref "U$19")
      (value "18AWG")
      (footprint "eagle-import:18AWG")
      (libsource (lib "eagle-import") (part "18AWG"))
    )
    (comp (ref "U$22")
      (value "18AWG")
      (footprint "eagle-import:18AWG")
      (libsource (lib "eagle-import") (part "18AWG"))
    )
    (comp (ref "U$23")
      (value "18AWG")
      (footprint "eagle-import:18AWG")
      (libsource (lib "eagle-import") (part "18AWG"))
    )
    (comp (ref "U$24")
      (value "18AWG")
      (footprint "eagle-import:18AWG")
      (libsource (lib "eagle-import") (part "18AWG"))
    )
    (comp (ref "U$27")
      (value "18AWG")
      (footprint "eagle-import:18AWG")
      (libsource (lib "eagle-import") (part "18AWG"))
    )
    (comp (ref "U$30")
      (value "SWITCH_SPDT_TH")
      (footprint "eagle-import:SWITCH_SPDT_PTH_11.6X4.0MM_LOCK")
      (libsource (lib "eagle-import") (part "SWITCH_SPDT_TH"))
    )
    (comp (ref "C1")
      (value "0.1uF")
      (footprint "eagle-import:C0603")
      (libsource (lib "eagle-import") (part "CAPACITOR0603"))
    )
    (comp (ref "C1M1")
      (value "33nF")
      (footprint "eagle-import:C0603")
      (libsource (lib "eagle-import") (part "CAPACITOR0603"))
    )
    (comp (ref "C1M2")
      (value "33nF")
      (footprint "eagle-import:C0603")
      (libsource (lib "eagle-import") (part "CAPACITOR0603"))
    )
    (comp (ref "C1M3")
      (value "33nF")
      (footprint "eagle-import:C0603")
      (libsource (lib "eagle-import") (part "CAPACITOR0603"))
    )
    (comp (ref "C1M4")
      (value "33nF")
      (footprint "eagle-import:C0603")
      (libsource (lib "eagle-import") (part "CAPACITOR0603"))
    )
    (comp (ref "C2")
      (value "0.1uF")
      (footprint "eagle-import:C0603")
      (libsource (lib "eagle-import") (part "CAPACITOR0603"))
    )
    (comp (ref "C2M1")
      (value "680uF")
      (footprint "eagle-import:E3,5-8")
      (libsource (lib "eagle-import") (part "CPOL-USE3.5-8"))
    )
    (comp (ref "C2M2")
      (value "680uF")
      (footprint "eagle-import:E3,5-8")
      (libsource (lib "eagle-import") (part "CPOL-USE3.5-8"))
    )
    (comp (ref "C2M3")
      (value "680uF")
      (footprint "eagle-import:E3,5-8")
      (libsource (lib "eagle-import") (part "CPOL-USE3.5-8"))
    )
    (comp (ref "C2M4")
      (value "680uF")
      (footprint "eagle-import:E3,5-8")
      (libsource (lib "eagle-import") (part "CPOL-USE3.5-8"))
    )
    (comp (ref "C3M1")
      (value "1uF")
      (footprint "eagle-import:C0603")
      (libsource (lib "eagle-import") (part "CAPACITOR0603"))
    )
    (comp (ref "C3M2")
      (value "1uF")
      (footprint "eagle-import:C0603")
      (libsource (lib "eagle-import") (part "CAPACITOR0603"))
    )
    (comp (ref "C3M3")
      (value "1uF")
      (footprint "eagle-import:C0603")
      (libsource (lib "eagle-import") (part "CAPACITOR0603"))
    )
    (comp (ref "C3M4")
      (value "1uF")
      (footprint "eagle-import:C0603")
      (libsource (lib "eagle-import") (part "CAPACITOR0603"))
    )
    (comp (ref "CONN_M1")
      (value "XT30PB-F")
      (footprint "eagle-import:XT30PB-F")
      (libsource (lib "eagle-import") (part "XT30PB-F"))
    )
    (comp (ref "CONN_M2")
      (value "XT30PB-F")
      (footprint "eagle-import:XT30PB-F")
      (libsource (lib "eagle-import") (part "XT30PB-F"))
    )
    (comp (ref "CONN_M3")
      (value "XT30PB-F")
      (footprint "eagle-import:XT30PB-F")
      (libsource (lib "eagle-import") (part "XT30PB-F"))
    )
    (comp (ref "CONN_M4")
      (value "XT30PB-F")
      (footprint "eagle-import:XT30PB-F")
      (libsource (lib "eagle-import") (part "XT30PB-F"))
    )
    (comp (ref "D1M1")
      (value "GREEN")
      (footprint "eagle-import:LED-0603")
      (libsource (lib "eagle-import") (part "LED0603"))
    )
    (comp (ref "D1M2")
      (value "GREEN")
      (footprint "eagle-import:LED-0603")
      (libsource (lib "eagle-import") (part "LED0603"))
    )
    (comp (ref "D1M3")
      (value "GREEN")
      (footprint "eagle-import:LED-0603")
      (libsource (lib "eagle-import") (part "LED0603"))
    )
    (comp (ref "D1M4")
      (value "GREEN")
      (footprint "eagle-import:LED-0603")
      (libsource (lib "eagle-import") (part "LED0603"))
    )
    (comp (ref "D2M1")
      (value "RED")
      (footprint "eagle-import:LED-0603")
      (libsource (lib "eagle-import") (part "LED0603"))
    )
    (comp (ref "D2M2")
      (value "RED")
      (footprint "eagle-import:LED-0603")
      (libsource (lib "eagle-import") (part "LED0603"))
    )
    (comp (ref "D2M3")
      (value "RED")
      (footprint "eagle-import:LED-0603")
      (libsource (lib "eagle-import") (part "LED0603"))
    )
    (comp (ref "D2M4")
      (value "RED")
      (footprint "eagle-import:LED-0603")
      (libsource (lib "eagle-import") (part "LED0603"))
    )
    (comp (ref "J3")
      (value "14AWG")
      (footprint "eagle-import:14AWG")
      (libsource (lib "eagle-import") (part "14AWG"))
    )
    (comp (ref "J4")
      (value "14AWG")
      (footprint "eagle-import:14AWG")
      (libsource (lib "eagle-import") (part "14AWG"))
    )
    (comp (ref "J5")
      (value "14AWG")
      (footprint "eagle-import:14AWG")
      (libsource (lib "eagle-import") (part "14AWG"))
    )
    (comp (ref "J16")
      (value "14AWG")
      (footprint "eagle-import:14AWG")
      (libsource (lib "eagle-import") (part "14AWG"))
    )
    (comp (ref "J17")
      (value "14AWG")
      (footprint "eagle-import:14AWG")
      (libsource (lib "eagle-import") (part "14AWG"))
    )
    (comp (ref "J18")
      (value "14AWG")
      (footprint "eagle-import:14AWG")
      (libsource (lib "eagle-import") (part "14AWG"))
    )
    (comp (ref "J19")
      (value "14AWG")
      (footprint "eagle-import:14AWG")
      (libsource (lib "eagle-import") (part "14AWG"))
    )
    (comp (ref "Q1M1")
      (value "AOD482")
      (footprint "eagle-import:DPAK")
      (libsource (lib "eagle-import") (part "MOSFET-NCH-DPAK"))
    )
    (comp (ref "Q1M2")
      (value "AOD482")
      (footprint "eagle-import:DPAK")
      (libsource (lib "eagle-import") (part "MOSFET-NCH-DPAK"))
    )
    (comp (ref "Q1M3")
      (value "AOD482")
      (footprint "eagle-import:DPAK")
      (libsource (lib "eagle-import") (part "MOSFET-NCH-DPAK"))
    )
    (comp (ref "Q1M4")
      (value "AOD482")
      (footprint "eagle-import:DPAK")
      (libsource (lib "eagle-import") (part "MOSFET-NCH-DPAK"))
    )
    (comp (ref "R1M1")
      (value "3.24k")
      (footprint "eagle-import:R0603")
      (libsource (lib "eagle-import") (part "RESISTOR0603"))
    )
    (comp (ref "R1M2")
      (value "3.24k")
      (footprint "eagle-import:R0603")
      (libsource (lib "eagle-import") (part "RESISTOR0603"))
    )
    (comp (ref "R1M3")
      (value "3.24k")
      (footprint "eagle-import:R0603")
      (libsource (lib "eagle-import") (part "RESISTOR0603"))
    )
    (comp (ref "R1M4")
      (value "3.24k")
      (footprint "eagle-import:R0603")
      (libsource (lib "eagle-import") (part "RESISTOR0603"))
    )
    (comp (ref "R2M1")
      (value "3.24k")
      (footprint "eagle-import:R0603")
      (libsource (lib "eagle-import") (part "RESISTOR0603"))
    )
    (comp (ref "R2M2")
      (value "3.24k")
      (footprint "eagle-import:R0603")
      (libsource (lib "eagle-import") (part "RESISTOR0603"))
    )
    (comp (ref "R2M3")
      (value "3.24k")
      (footprint "eagle-import:R0603")
      (libsource (lib "eagle-import") (part "RESISTOR0603"))
    )
    (comp (ref "R2M4")
      (value "3.24k")
      (footprint "eagle-import:R0603")
      (libsource (lib "eagle-import") (part "RESISTOR0603"))
    )
    (comp (ref "R5M1")
      (value "1k")
      (footprint "eagle-import:R0603")
      (libsource (lib "eagle-import") (part "RESISTOR0603"))
    )
    (comp (ref "R5M2")
      (value "1k")
      (footprint "eagle-import:R0603")
      (libsource (lib "eagle-import") (part "RESISTOR0603"))
    )
    (comp (ref "R5M3")
      (value "1k")
      (footprint "eagle-import:R0603")
      (libsource (lib "eagle-import") (part "RESISTOR0603"))
    )
    (comp (ref "R5M4")
      (value "1k")
      (footprint "eagle-import:R0603")
      (libsource (lib "eagle-import") (part "RESISTOR0603"))
    )
    (comp (ref "R6M1")
      (value "1k")
      (footprint "eagle-import:R0603")
      (libsource (lib "eagle-import") (part "RESISTOR0603"))
    )
    (comp (ref "R6M2")
      (value "1k")
      (footprint "eagle-import:R0603")
      (libsource (lib "eagle-import") (part "RESISTOR0603"))
    )
    (comp (ref "R6M3")
      (value "1k")
      (footprint "eagle-import:R0603")
      (libsource (lib "eagle-import") (part "RESISTOR0603"))
    )
    (comp (ref "R6M4")
      (value "1k")
      (footprint "eagle-import:R0603")
      (libsource (lib "eagle-import") (part "RESISTOR0603"))
    )
    (comp (ref "R7M1")
      (value "1k")
      (footprint "eagle-import:R0603")
      (libsource (lib "eagle-import") (part "RESISTOR0603"))
    )
    (comp (ref "R7M2")
      (value "1k")
      (footprint "eagle-import:R0603")
      (libsource (lib "eagle-import") (part "RESISTOR0603"))
    )
    (comp (ref "R7M3")
      (value "1k")
      (footprint "eagle-import:R0603")
      (libsource (lib "eagle-import") (part "RESISTOR0603"))
    )
    (comp (ref "R7M4")
      (value "1k")
      (footprint "eagle-import:R0603")
      (libsource (lib "eagle-import") (part "RESISTOR0603"))
    )
    (comp (ref "R8M1")
      (value "10k")
      (footprint "eagle-import:R0603")
      (libsource (lib "eagle-import") (part "RESISTOR0603"))
    )
    (comp (ref "R8M2")
      (value "10k")
      (footprint "eagle-import:R0603")
      (libsource (lib "eagle-import") (part "RESISTOR0603"))
    )
    (comp (ref "R8M3")
      (value "10k")
      (footprint "eagle-import:R0603")
      (libsource (lib "eagle-import") (part "RESISTOR0603"))
    )
    (comp (ref "R8M4")
      (value "10k")
      (footprint "eagle-import:R0603")
      (libsource (lib "eagle-import") (part "RESISTOR0603"))
    )
    (comp (ref "R9M1")
      (value "10k")
      (footprint "eagle-import:R0603")
      (libsource (lib "eagle-import") (part "RESISTOR0603"))
    )
    (comp (ref "R9M2")
      (value "10k")
      (footprint "eagle-import:R0603")
      (libsource (lib "eagle-import") (part "RESISTOR0603"))
    )
    (comp (ref "R9M3")
      (value "10k")
      (footprint "eagle-import:R0603")
      (libsource (lib "eagle-import") (part "RESISTOR0603"))
    )
    (comp (ref "R9M4")
      (value "10k")
      (footprint "eagle-import:R0603")
      (libsource (lib "eagle-import") (part "RESISTOR0603"))
    )
    (comp (ref "R10M1")
      (value "1k")
      (footprint "eagle-import:R0603")
      (libsource (lib "eagle-import") (part "RESISTOR0603"))
    )
    (comp (ref "R10M2")
      (value "1k")
      (footprint "eagle-import:R0603")
      (libsource (lib "eagle-import") (part "RESISTOR0603"))
    )
    (comp (ref "R10M3")
      (value "1k")
      (footprint "eagle-import:R0603")
      (libsource (lib "eagle-import") (part "RESISTOR0603"))
    )
    (comp (ref "R10M4")
      (value "1k")
      (footprint "eagle-import:R0603")
      (libsource (lib "eagle-import") (part "RESISTOR0603"))
    )
    (comp (ref "R11M1")
      (value "10k")
      (footprint "eagle-import:R0603")
      (libsource (lib "eagle-import") (part "RESISTOR0603"))
    )
    (comp (ref "R11M2")
      (value "10k")
      (footprint "eagle-import:R0603")
      (libsource (lib "eagle-import") (part "RESISTOR0603"))
    )
    (comp (ref "R11M3")
      (value "10k")
      (footprint "eagle-import:R0603")
      (libsource (lib "eagle-import") (part "RESISTOR0603"))
    )
    (comp (ref "R11M4")
      (value "10k")
      (footprint "eagle-import:R0603")
      (libsource (lib "eagle-import") (part "RESISTOR0603"))
    )
    (comp (ref "R12M1")
      (value "4.7k")
      (footprint "eagle-import:R0603")
      (libsource (lib "eagle-import") (part "RESISTOR0603"))
    )
    (comp (ref "R12M2")
      (value "4.7k")
      (footprint "eagle-import:R0603")
      (libsource (lib "eagle-import") (part "RESISTOR0603"))
    )
    (comp (ref "R12M3")
      (value "4.7k")
      (footprint "eagle-import:R0603")
      (libsource (lib "eagle-import") (part "RESISTOR0603"))
    )
    (comp (ref "R12M4")
      (value "4.7k")
      (footprint "eagle-import:R0603")
      (libsource (lib "eagle-import") (part "RESISTOR0603"))
    )
    (comp (ref "U$4")
      (value "74LVC2G")
      (footprint "eagle-import:SOT23-6")
      (libsource (lib "eagle-import") (part "74LVC2G"))
    )
    (comp (ref "U$5")
      (value "74LVC2G")
      (footprint "eagle-import:SOT23-6")
      (libsource (lib "eagle-import") (part "74LVC2G"))
    )
    (comp (ref "U1M1")
      (value "VNH5019")
      (footprint "eagle-import:POWERSO-30")
      (libsource (lib "eagle-import") (part "VNH5019"))
    )
    (comp (ref "U1M2")
      (value "VNH5019")
      (footprint "eagle-import:POWERSO-30")
      (libsource (lib "eagle-import") (part "VNH5019"))
    )
    (comp (ref "U1M3")
      (value "VNH5019")
      (footprint "eagle-import:POWERSO-30")
      (libsource (lib "eagle-import") (part "VNH5019"))
    )
    (comp (ref "U1M4")
      (value "VNH5019")
      (footprint "eagle-import:POWERSO-30")
      (libsource (lib "eagle-import") (part "VNH5019"))
    )
    (comp (ref "1C7")
      (value "1uF")
      (footprint "eagle-import:C0603")
      (libsource (lib "eagle-import") (part "CAPACITOR0603"))
    )
    (comp (ref "1C8")
      (value "1uF")
      (footprint "eagle-import:C0603")
      (libsource (lib "eagle-import") (part "CAPACITOR0603"))
    )
    (comp (ref "1C9")
      (value "20pF")
      (footprint "eagle-import:C0603")
      (libsource (lib "eagle-import") (part "CAPACITOR0603"))
    )
    (comp (ref "1C10")
      (value "20pF")
      (footprint "eagle-import:C0603")
      (libsource (lib "eagle-import") (part "CAPACITOR0603"))
    )
    (comp (ref "1C11")
      (value "1uF")
      (footprint "eagle-import:C0603")
      (libsource (lib "eagle-import") (part "CAPACITOR0603"))
    )
    (comp (ref "1C12")
      (value "1uF")
      (footprint "eagle-import:C0603")
      (libsource (lib "eagle-import") (part "CAPACITOR0603"))
    )
    (comp (ref "1D0")
      (value "BLUE")
      (footprint "eagle-import:LED-0603")
      (libsource (lib "eagle-import") (part "LED0603"))
    )
    (comp (ref "1OSC")
      (value "8MHz")
      (footprint "eagle-import:CRYSTAL-SMD-5X3.2-2PAD")
      (libsource (lib "eagle-import") (part "CRYSTAL_5032"))
    )
    (comp (ref "1R8")
      (value "1k")
      (footprint "eagle-import:R0603")
      (libsource (lib "eagle-import") (part "RESISTOR0603"))
    )
    (comp (ref "1R9")
      (value "10k")
      (footprint "eagle-import:R0603")
      (libsource (lib "eagle-import") (part "RESISTOR0603"))
    )
    (comp (ref "1R10")
      (value "1k")
      (footprint "eagle-import:R0603")
      (libsource (lib "eagle-import") (part "RESISTOR0603"))
    )
    (comp (ref "1R11")
      (value "10k")
      (footprint "eagle-import:R0603")
      (libsource (lib "eagle-import") (part "RESISTOR0603"))
    )
    (comp (ref "1SW1")
      (value "MOMENTARY_SWITCH_4X3")
      (footprint "eagle-import:MOMENTARY_SWITCH_4X3")
      (libsource (lib "eagle-import") (part "MOMENTARY_SWITCH_4X3"))
    )
    (comp (ref "1U4")
      (value "STM32F103CBT6")
      (footprint "eagle-import:LQFP48")
      (libsource (lib "eagle-import") (part "STM32F103CBT6"))
    )
    (comp (ref "FB1")
      (value "FERRITE_BEAD")
      (footprint "eagle-import:R0603")
      (libsource (lib "eagle-import") (part "FERRITE_BEAD"))
    )
    (comp (ref "FB2")
      (value "FERRITE_BEAD")
      (footprint "eagle-import:R0603")
      (libsource (lib "eagle-import") (part "FERRITE_BEAD"))
    )
    (comp (ref "J2")
      (value "CONN_04LOCK")
      (footprint "eagle-import:1X04_LOCK")
      (libsource (lib "eagle-import") (part "CONN_04LOCK"))
    )
    (comp (ref "SWD")
      (value "BM06B-SRSS-TB")
      (footprint "eagle-import:BM06B-SRSS-TB")
      (libsource (lib "eagle-import") (part "BM06B-SRSS-TB"))
    )
    (comp (ref "U$31")
      (value "SWITCH_SPDT_TH")
      (footprint "eagle-import:SWITCH_SPDT_PTH_11.6X4.0MM_LOCK")
      (libsource (lib "eagle-import") (part "SWITCH_SPDT_TH"))
    )
    (comp (ref "X1")
      (value "BM10B-SRSS-TB")
      (footprint "eagle-import:BM10B-SRSS-TB")
      (libsource (lib "eagle-import") (part "BM10B-SRSS-TB"))
    )
  )
  (nets
    (net (code "1") (name "3.3V") (class "Default")
      (node (ref "2C4") (pin "+") (pinfunction "+_+") (pintype "passive"))
      (node (ref "2C5") (pin "1") (pinfunction "1_1") (pintype "passive"))
      (node (ref "2L1") (pin "P2") (pinfunction "2_P2") (pintype "passive"))
      (node (ref "2R1") (pin "2") (pinfunction "2_2") (pintype "passive"))
      (node (ref "C1") (pin "1") (pinfunction "1_1") (pintype "passive"))
      (node (ref "C2") (pin "1") (pinfunction "1_1") (pintype "passive"))
      (node (ref "J2") (pin "3") (pinfunction "3_3") (pintype "passive"))
      (node (ref "J2") (pin "4") (pinfunction "4_4") (pintype "passive"))
      (node (ref "MOUSE") (pin "1") (pinfunction "1_1") (pintype "passive"))
      (node (ref "R1M1") (pin "2") (pinfunction "2_2") (pintype "passive"))
      (node (ref "R1M2") (pin "2") (pinfunction "2_2") (pintype "passive"))
      (node (ref "R1M3") (pin "2") (pinfunction "2_2") (pintype "passive"))
      (node (ref "R1M4") (pin "2") (pinfunction "2_2") (pintype "passive"))
      (node (ref "R2M1") (pin "2") (pinfunction "2_2") (pintype "passive"))
      (node (ref "R2M2") (pin "2") (pinfunction "2_2") (pintype "passive"))
      (node (ref "R2M3") (pin "2") (pinfunction "2_2") (pintype "passive"))
      (node (ref "R2M4") (pin "2") (pinfunction "2_2") (pintype "passive"))
      (node (ref "U$28") (pin "P$1") (pinfunction "1_P$1") (pintype "passive"))
      (node (ref "U$31") (pin "1") (pinfunction "O_1") (pintype "passive"))
      (node (ref "U$4") (pin "5") (pinfunction "P$V+_5") (pintype "bidirectional"))
      (node (ref "U$5") (pin "5") (pinfunction "P$V+_5") (pintype "bidirectional"))
    )
    (net (code "2") (name "3.3V_MCU") (class "Default")
      (node (ref "1C11") (pin "1") (pinfunction "1_1") (pintype "passive"))
      (node (ref "1C7") (pin "1") (pinfunction "1_1") (pintype "passive"))
      (node (ref "1C8") (pin "1") (pinfunction "1_1") (pintype "passive"))
      (node (ref "1R9") (pin "2") (pinfunction "2_2") (pintype "passive"))
      (node (ref "1U4") (pin "24") (pinfunction "VDD_1_24") (pintype "power_in"))
      (node (ref "1U4") (pin "36") (pinfunction "VDD_2_36") (pintype "power_in"))
      (node (ref "1U4") (pin "48") (pinfunction "VDD_3_48") (pintype "power_in"))
      (node (ref "FB2") (pin "2") (pinfunction "2_2") (pintype "passive"))
      (node (ref "U$31") (pin "2") (pinfunction "P_2") (pintype "passive"))
    )
    (net (code "3") (name "3.3V_PROG") (class "Default")
      (node (ref "SWD") (pin "4") (pinfunction "4_4") (pintype "passive"))
      (node (ref "U$31") (pin "3") (pinfunction "S_3") (pintype "passive"))
    )
    (net (code "4") (name "12V") (class "Default")
      (node (ref "2C1") (pin "1") (pinfunction "1_1") (pintype "passive"))
      (node (ref "2C2") (pin "1") (pinfunction "1_1") (pintype "passive"))
      (node (ref "2U1") (pin "7") (pinfunction "VIN_7") (pintype "power_in"))
      (node (ref "U$15") (pin "P$1") (pinfunction "1_P$1") (pintype "passive"))
    )
    (net (code "5") (name "33") (class "Default")
      (node (ref "1R8") (pin "2") (pinfunction "2_2") (pintype "passive"))
      (node (ref "1U4") (pin "19") (pinfunction "PB1/ADC12_IN9/TIM3_CH4_19") (pintype "bidirectional"))
    )
    (net (code "6") (name "AGND") (class "Default")
      (node (ref "1C1") (pin "2") (pinfunction "2_2") (pintype "passive"))
      (node (ref "1C12") (pin "1") (pinfunction "1_1") (pintype "passive"))
      (node (ref "1C13") (pin "2") (pinfunction "2_2") (pintype "passive"))
      (node (ref "1C14") (pin "2") (pinfunction "2_2") (pintype "passive"))
      (node (ref "1C15") (pin "2") (pinfunction "2_2") (pintype "passive"))
      (node (ref "1C16") (pin "2") (pinfunction "2_2") (pintype "passive"))
      (node (ref "1C17") (pin "2") (pinfunction "2_2") (pintype "passive"))
      (node (ref "1C2") (pin "2") (pinfunction "2_2") (pintype "passive"))
      (node (ref "1C3") (pin "2") (pinfunction "2_2") (pintype "passive"))
      (node (ref "1C4") (pin "2") (pinfunction "2_2") (pintype "passive"))
      (node (ref "1C5") (pin "2") (pinfunction "2_2") (pintype "passive"))
      (node (ref "1C6") (pin "2") (pinfunction "2_2") (pintype "passive"))
      (node (ref "1R12") (pin "1") (pinfunction "1_1") (pintype "passive"))
      (node (ref "1R13") (pin "1") (pinfunction "1_1") (pintype "passive"))
      (node (ref "1R14") (pin "1") (pinfunction "1_1") (pintype "passive"))
      (node (ref "1R15") (pin "1") (pinfunction "1_1") (pintype "passive"))
      (node (ref "1R16") (pin "1") (pinfunction "1_1") (pintype "passive"))
      (node (ref "1R2") (pin "1") (pinfunction "1_1") (pintype "passive"))
      (node (ref "1R3") (pin "1") (pinfunction "1_1") (pintype "passive"))
      (node (ref "1R4") (pin "1") (pinfunction "1_1") (pintype "passive"))
      (node (ref "1R5") (pin "1") (pinfunction "1_1") (pintype "passive"))
      (node (ref "1R6") (pin "1") (pinfunction "1_1") (pintype "passive"))
      (node (ref "1R7") (pin "1") (pinfunction "1_1") (pintype "passive"))
      (node (ref "1U1") (pin "12") (pinfunction "GND_12") (pintype "bidirectional"))
      (node (ref "1U2") (pin "12") (pinfunction "GND_12") (pintype "bidirectional"))
      (node (ref "1U3") (pin "12") (pinfunction "GND_12") (pintype "bidirectional"))
      (node (ref "1U4") (pin "8") (pinfunction "VSS_A_8") (pintype "power_in"))
      (node (ref "FB1") (pin "1") (pinfunction "1_1") (pintype "passive"))
      (node (ref "R3") (pin "1") (pinfunction "1_1") (pintype "passive"))
      (node (ref "R4") (pin "1") (pinfunction "1_1") (pintype "passive"))
      (node (ref "R5") (pin "1") (pinfunction "1_1") (pintype "passive"))
      (node (ref "R6") (pin "1") (pinfunction "1_1") (pintype "passive"))
      (node (ref "R7") (pin "1") (pinfunction "1_1") (pintype "passive"))
      (node (ref "R8") (pin "1") (pinfunction "1_1") (pintype "passive"))
    )
    (net (code "7") (name "BATT_LVL") (class "Default")
      (node (ref "1U4") (pin "2") (pinfunction "PC13-TAMPER-RTC_2") (pintype "input"))
      (node (ref "R1") (pin "1") (pinfunction "1_1") (pintype "passive"))
      (node (ref "R2") (pin "1") (pinfunction "1_1") (pintype "passive"))
    )
    (net (code "8") (name "CPM1") (class "Default")
      (node (ref "Q1M1") (pin "1") (pinfunction "G_1") (pintype "bidirectional"))
      (node (ref "U1M1") (pin "P11") (pinfunction "CP_P11") (pintype "output"))
    )
    (net (code "9") (name "CPM2") (class "Default")
      (node (ref "Q1M2") (pin "1") (pinfunction "G_1") (pintype "bidirectional"))
      (node (ref "U1M2") (pin "P11") (pinfunction "CP_P11") (pintype "output"))
    )
    (net (code "10") (name "CPM3") (class "Default")
      (node (ref "Q1M3") (pin "1") (pinfunction "G_1") (pintype "bidirectional"))
      (node (ref "U1M3") (pin "P11") (pinfunction "CP_P11") (pintype "output"))
    )
    (net (code "11") (name "CPM4") (class "Default")
      (node (ref "Q1M4") (pin "1") (pinfunction "G_1") (pintype "bidirectional"))
      (node (ref "U1M4") (pin "P11") (pinfunction "CP_P11") (pintype "output"))
    )
    (net (code "12") (name "CSDIS1") (class "Default")
      (node (ref "R9M1") (pin "1") (pinfunction "1_1") (pintype "passive"))
      (node (ref "U1M1") (pin "P6") (pinfunction "CS_DIS_P6") (pintype "input"))
    )
    (net (code "13") (name "CSDIS2") (class "Default")
      (node (ref "R9M2") (pin "1") (pinfunction "1_1") (pintype "passive"))
      (node (ref "U1M2") (pin "P6") (pinfunction "CS_DIS_P6") (pintype "input"))
    )
    (net (code "14") (name "CSDIS3") (class "Default")
      (node (ref "R9M3") (pin "1") (pinfunction "1_1") (pintype "passive"))
      (node (ref "U1M3") (pin "P6") (pinfunction "CS_DIS_P6") (pintype "input"))
    )
    (net (code "15") (name "CSDIS4") (class "Default")
      (node (ref "R9M4") (pin "1") (pinfunction "1_1") (pintype "passive"))
      (node (ref "U1M4") (pin "P6") (pinfunction "CS_DIS_P6") (pintype "input"))
    )
    (net (code "16") (name "CSM1") (class "Default")
      (node (ref "1U3") (pin "20") (pinfunction "CHAN11_20") (pintype "bidirectional"))
      (node (ref "C1M1") (pin "2") (pinfunction "2_2") (pintype "passive"))
      (node (ref "R8M1") (pin "1") (pinfunction "1_1") (pintype "passive"))
    )
    (net (code "17") (name "CSM2") (class "Default")
      (node (ref "1U3") (pin "17") (pinfunction "CHAN14_17") (pintype "bidirectional"))
      (node (ref "C1M2") (pin "2") (pinfunction "2_2") (pintype "passive"))
      (node (ref "R8M2") (pin "1") (pinfunction "1_1") (pintype "passive"))
    )
    (net (code "18") (name "CSM3") (class "Default")
      (node (ref "1U3") (pin "2") (pinfunction "CHAN7_2") (pintype "bidirectional"))
      (node (ref "C1M3") (pin "2") (pinfunction "2_2") (pintype "passive"))
      (node (ref "R8M3") (pin "1") (pinfunction "1_1") (pintype "passive"))
    )
    (net (code "19") (name "CSM4") (class "Default")
      (node (ref "1U3") (pin "3") (pinfunction "CHAN6_3") (pintype "bidirectional"))
      (node (ref "C1M4") (pin "2") (pinfunction "2_2") (pintype "passive"))
      (node (ref "R8M4") (pin "1") (pinfunction "1_1") (pintype "passive"))
    )
    (net (code "20") (name "DEBUG_RX") (class "Default")
      (node (ref "1U4") (pin "13") (pinfunction "PA3/USART2_RX/ADC12_IN3/TIM2_CH4_13") (pintype "bidirectional"))
      (node (ref "SWD") (pin "6") (pinfunction "6_6") (pintype "passive"))
    )
    (net (code "21") (name "DEBUG_TX") (class "Default")
      (node (ref "1U4") (pin "12") (pinfunction "PA2/USART2_TX/ADC12_IN2/TIM2_CH3_12") (pintype "bidirectional"))
      (node (ref "SWD") (pin "5") (pinfunction "5_5") (pintype "passive"))
    )
    (net (code "22") (name "FDBK") (class "Default")
      (node (ref "3POT1") (pin "1") (pinfunction "CCW_1") (pintype "passive"))
      (node (ref "3POT1") (pin "2") (pinfunction "WIPER_2") (pintype "passive"))
      (node (ref "3R2") (pin "2") (pinfunction "2_2") (pintype "passive"))
      (node (ref "3U1") (pin "P2") (pinfunction "FDBK_P2") (pintype "input"))
    )
    (net (code "23") (name "GATE1") (class "Default")
      (node (ref "1U3") (pin "21") (pinfunction "CHAN10_21") (pintype "bidirectional"))
      (node (ref "GATE1") (pin "2") (pinfunction "2_2") (pintype "passive"))
      (node (ref "R3") (pin "2") (pinfunction "2_2") (pintype "passive"))
    )
    (net (code "24") (name "GATE2") (class "Default")
      (node (ref "1U3") (pin "9") (pinfunction "CHAN0_9") (pintype "bidirectional"))
      (node (ref "GATE2") (pin "2") (pinfunction "2_2") (pintype "passive"))
      (node (ref "R4") (pin "2") (pinfunction "2_2") (pintype "passive"))
    )
    (net (code "25") (name "GND") (class "Default")
      (node (ref "1C10") (pin "2") (pinfunction "2_2") (pintype "passive"))
      (node (ref "1C11") (pin "2") (pinfunction "2_2") (pintype "passive"))
      (node (ref "1C7") (pin "2") (pinfunction "2_2") (pintype "passive"))
      (node (ref "1C8") (pin "2") (pinfunction "2_2") (pintype "passive"))
      (node (ref "1C9") (pin "2") (pinfunction "2_2") (pintype "passive"))
      (node (ref "1D0") (pin "C") (pinfunction "C_C") (pintype "passive"))
      (node (ref "1D1") (pin "C") (pinfunction "C_C") (pintype "passive"))
      (node (ref "1D10") (pin "C") (pinfunction "C_C") (pintype "passive"))
      (node (ref "1D11") (pin "C") (pinfunction "C_C") (pintype "passive"))
      (node (ref "1D12") (pin "C") (pinfunction "C_C") (pintype "passive"))
      (node (ref "1D13") (pin "C") (pinfunction "C_C") (pintype "passive"))
      (node (ref "1D14") (pin "C") (pinfunction "C_C") (pintype "passive"))
      (node (ref "1D15") (pin "C") (pinfunction "C_C") (pintype "passive"))
      (node (ref "1D16") (pin "C") (pinfunction "C_C") (pintype "passive"))
      (node (ref "1D17") (pin "C") (pinfunction "C_C") (pintype "passive"))
      (node (ref "1D18") (pin "C") (pinfunction "C_C") (pintype "passive"))
      (node (ref "1D19") (pin "C") (pinfunction "C_C") (pintype "passive"))
      (node (ref "1D2") (pin "C") (pinfunction "C_C") (pintype "passive"))
      (node (ref "1D20") (pin "C") (pinfunction "C_C") (pintype "passive"))
      (node (ref "1D21") (pin "C") (pinfunction "C_C") (pintype "passive"))
      (node (ref "1D22") (pin "C") (pinfunction "C_C") (pintype "passive"))
      (node (ref "1D23") (pin "C") (pinfunction "C_C") (pintype "passive"))
      (node (ref "1D24") (pin "C") (pinfunction "C_C") (pintype "passive"))
      (node (ref "1D25") (pin "C") (pinfunction "C_C") (pintype "passive"))
      (node (ref "1D26") (pin "C") (pinfunction "C_C") (pintype "passive"))
      (node (ref "1D27") (pin "C") (pinfunction "C_C") (pintype "passive"))
      (node (ref "1D28") (pin "C") (pinfunction "C_C") (pintype "passive"))
      (node (ref "1D29") (pin "C") (pinfunction "C_C") (pintype "passive"))
      (node (ref "1D3") (pin "C") (pinfunction "C_C") (pintype "passive"))
      (node (ref "1D30") (pin "C") (pinfunction "C_C") (pintype "passive"))
      (node (ref "1D31") (pin "C") (pinfunction "C_C") (pintype "passive"))
      (node (ref "1D32") (pin "C") (pinfunction "C_C") (pintype "passive"))
      (node (ref "1D33") (pin "C") (pinfunction "C_C") (pintype "passive"))
      (node (ref "1D34") (pin "C") (pinfunction "C_C") (pintype "passive"))
      (node (ref "1D35") (pin "C") (pinfunction "C_C") (pintype "passive"))
      (node (ref "1D36") (pin "C") (pinfunction "C_C") (pintype "passive"))
      (node (ref "1D38") (pin "C") (pinfunction "C_C") (pintype "passive"))
      (node (ref "1D4") (pin "C") (pinfunction "C_C") (pintype "passive"))
      (node (ref "1D40") (pin "C") (pinfunction "C_C") (pintype "passive"))
      (node (ref "1D5") (pin "C") (pinfunction "C_C") (pintype "passive"))
      (node (ref "1D6") (pin "C") (pinfunction "C_C") (pintype "passive"))
      (node (ref "1D7") (pin "C") (pinfunction "C_C") (pintype "passive"))
      (node (ref "1D8") (pin "C") (pinfunction "C_C") (pintype "passive"))
      (node (ref "1D9") (pin "C") (pinfunction "C_C") (pintype "passive"))
      (node (ref "1R10") (pin "1") (pinfunction "1_1") (pintype "passive"))
      (node (ref "1R11") (pin "2") (pinfunction "2_2") (pintype "passive"))
      (node (ref "1U4") (pin "23") (pinfunction "VSS_1_23") (pintype "power_in"))
      (node (ref "1U4") (pin "35") (pinfunction "VSS_2_35") (pintype "power_in"))
      (node (ref "1U4") (pin "47") (pinfunction "VSS_3_47") (pintype "power_in"))
      (node (ref "2C1") (pin "2") (pinfunction "2_2") (pintype "passive"))
      (node (ref "2C2") (pin "2") (pinfunction "2_2") (pintype "passive"))
      (node (ref "2C4") (pin "-") (pinfunction "-_-") (pintype "passive"))
      (node (ref "2C5") (pin "2") (pinfunction "2_2") (pintype "passive"))
      (node (ref "2D1") (pin "A") (pinfunction "A_A") (pintype "passive"))
      (node (ref "2R2") (pin "1") (pinfunction "1_1") (pintype "passive"))
      (node (ref "2U1") (pin "6") (pinfunction "GND_6") (pintype "power_in"))
      (node (ref "2U1") (pin "9") (pinfunction "GND_9") (pintype "power_in"))
      (node (ref "2U1") (pin "P$1") (pinfunction "GND_P$1") (pintype "power_in"))
      (node (ref "2U1") (pin "P$2") (pinfunction "GND_P$2") (pintype "power_in"))
      (node (ref "2U1") (pin "P$3") (pinfunction "GND_P$3") (pintype "power_in"))
      (node (ref "2U1") (pin "P$4") (pinfunction "GND_P$4") (pintype "power_in"))
      (node (ref "2U1") (pin "P$5") (pinfunction "GND_P$5") (pintype "power_in"))
      (node (ref "2U1") (pin "P$6") (pinfunction "GND_P$6") (pintype "power_in"))
      (node (ref "3C1") (pin "-") (pinfunction "-_-") (pintype "passive"))
      (node (ref "3C2") (pin "2") (pinfunction "2_2") (pintype "passive"))
      (node (ref "3C3") (pin "-") (pinfunction "-_-") (pintype "passive"))
      (node (ref "3C4") (pin "-") (pinfunction "-_-") (pintype "passive"))
      (node (ref "3Q4") (pin "2") (pinfunction "S_2") (pintype "bidirectional"))
      (node (ref "3R2") (pin "1") (pinfunction "1_1") (pintype "passive"))
      (node (ref "3R9") (pin "1") (pinfunction "1_1") (pintype "passive"))
      (node (ref "3U1") (pin "P$1") (pinfunction "GND_P$1") (pintype "power_in"))
      (node (ref "3U1") (pin "P$10") (pinfunction "GND_P$10") (pintype "power_in"))
      (node (ref "3U1") (pin "P$11") (pinfunction "GND_P$11") (pintype "power_in"))
      (node (ref "3U1") (pin "P$12") (pinfunction "GND_P$12") (pintype "power_in"))
      (node (ref "3U1") (pin "P$13") (pinfunction "GND_P$13") (pintype "power_in"))
      (node (ref "3U1") (pin "P$14") (pinfunction "GND_P$14") (pintype "power_in"))
      (node (ref "3U1") (pin "P$15") (pinfunction "GND_P$15") (pintype "power_in"))
      (node (ref "3U1") (pin "P$16") (pinfunction "GND_P$16") (pintype "power_in"))
      (node (ref "3U1") (pin "P$17") (pinfunction "GND_P$17") (pintype "power_in"))
      (node (ref "3U1") (pin "P$18") (pinfunction "GND_P$18") (pintype "power_in"))
      (node (ref "3U1") (pin "P$19") (pinfunction "GND_P$19") (pintype "power_in"))
      (node (ref "3U1") (pin "P$2") (pinfunction "GND_P$2") (pintype "power_in"))
      (node (ref "3U1") (pin "P$20") (pinfunction "GND_P$20") (pintype "power_in"))
      (node (ref "3U1") (pin "P$3") (pinfunction "GND_P$3") (pintype "power_in"))
      (node (ref "3U1") (pin "P$4") (pinfunction "GND_P$4") (pintype "power_in"))
      (node (ref "3U1") (pin "P$5") (pinfunction "GND_P$5") (pintype "power_in"))
      (node (ref "3U1") (pin "P$6") (pinfunction "GND_P$6") (pintype "power_in"))
      (node (ref "3U1") (pin "P$7") (pinfunction "GND_P$7") (pintype "power_in"))
      (node (ref "3U1") (pin "P$8") (pinfunction "GND_P$8") (pintype "power_in"))
      (node (ref "3U1") (pin "P$9") (pinfunction "GND_P$9") (pintype "power_in"))
      (node (ref "3U1") (pin "P3") (pinfunction "GND_P3") (pintype "power_in"))
      (node (ref "3U1") (pin "TAB") (pinfunction "GND_TAB") (pintype "power_in"))
      (node (ref "C1") (pin "2") (pinfunction "2_2") (pintype "passive"))
      (node (ref "C1M1") (pin "1") (pinfunction "1_1") (pintype "passive"))
      (node (ref "C1M2") (pin "1") (pinfunction "1_1") (pintype "passive"))
      (node (ref "C1M3") (pin "1") (pinfunction "1_1") (pintype "passive"))
      (node (ref "C1M4") (pin "1") (pinfunction "1_1") (pintype "passive"))
      (node (ref "C2") (pin "2") (pinfunction "2_2") (pintype "passive"))
      (node (ref "C2M1") (pin "-") (pinfunction "-_-") (pintype "passive"))
      (node (ref "C2M2") (pin "-") (pinfunction "-_-") (pintype "passive"))
      (node (ref "C2M3") (pin "-") (pinfunction "-_-") (pintype "passive"))
      (node (ref "C2M4") (pin "-") (pinfunction "-_-") (pintype "passive"))
      (node (ref "C3") (pin "2") (pinfunction "2_2") (pintype "passive"))
      (node (ref "C3M1") (pin "2") (pinfunction "2_2") (pintype "passive"))
      (node (ref "C3M2") (pin "2") (pinfunction "2_2") (pintype "passive"))
      (node (ref "C3M3") (pin "2") (pinfunction "2_2") (pintype "passive"))
      (node (ref "C3M4") (pin "2") (pinfunction "2_2") (pintype "passive"))
      (node (ref "FB1") (pin "2") (pinfunction "2_2") (pintype "passive"))
      (node (ref "J12") (pin "1") (pinfunction "1_1") (pintype "passive"))
      (node (ref "J13") (pin "P$1") (pinfunction "1_P$1") (pintype "passive"))
      (node (ref "J14") (pin "P$1") (pinfunction "1_P$1") (pintype "passive"))
      (node (ref "J15") (pin "P$1") (pinfunction "1_P$1") (pintype "passive"))
      (node (ref "J16") (pin "P$1") (pinfunction "1_P$1") (pintype "passive"))
      (node (ref "J17") (pin "P$1") (pinfunction "1_P$1") (pintype "passive"))
      (node (ref "J18") (pin "P$1") (pinfunction "1_P$1") (pintype "passive"))
      (node (ref "J19") (pin "P$1") (pinfunction "1_P$1") (pintype "passive"))
      (node (ref "J2") (pin "2") (pinfunction "2_2") (pintype "passive"))
      (node (ref "J21") (pin "P$1") (pinfunction "1_P$1") (pintype "passive"))
      (node (ref "J6") (pin "P$1") (pinfunction "1_P$1") (pintype "passive"))
      (node (ref "LED1") (pin "2") (pinfunction "2_2") (pintype "passive"))
      (node (ref "LED2") (pin "2") (pinfunction "2_2") (pintype "passive"))
      (node (ref "MOUSE") (pin "2") (pinfunction "2_2") (pintype "passive"))
      (node (ref "R10M1") (pin "1") (pinfunction "1_1") (pintype "passive"))
      (node (ref "R10M2") (pin "1") (pinfunction "1_1") (pintype "passive"))
      (node (ref "R10M3") (pin "1") (pinfunction "1_1") (pintype "passive"))
      (node (ref "R10M4") (pin "1") (pinfunction "1_1") (pintype "passive"))
      (node (ref "R11M1") (pin "1") (pinfunction "1_1") (pintype "passive"))
      (node (ref "R11M2") (pin "1") (pinfunction "1_1") (pintype "passive"))
      (node (ref "R11M3") (pin "1") (pinfunction "1_1") (pintype "passive"))
      (node (ref "R11M4") (pin "1") (pinfunction "1_1") (pintype "passive"))
      (node (ref "R2") (pin "2") (pinfunction "2_2") (pintype "passive"))
      (node (ref "R9M1") (pin "2") (pinfunction "2_2") (pintype "passive"))
      (node (ref "R9M2") (pin "2") (pinfunction "2_2") (pintype "passive"))
      (node (ref "R9M3") (pin "2") (pinfunction "2_2") (pintype "passive"))
      (node (ref "R9M4") (pin "2") (pinfunction "2_2") (pintype "passive"))
      (node (ref "SWD") (pin "1") (pinfunction "1_1") (pintype "passive"))
      (node (ref "U$18") (pin "P$1") (pinfunction "1_P$1") (pintype "passive"))
      (node (ref "U$23") (pin "P$1") (pinfunction "1_P$1") (pintype "passive"))
      (node (ref "U$25") (pin "P$1") (pinfunction "1_P$1") (pintype "passive"))
      (node (ref "U$26") (pin "-") (pinfunction "P$V-_-") (pintype "bidirectional"))
      (node (ref "U$29") (pin "P$1") (pinfunction "1_P$1") (pintype "passive"))
      (node (ref "U$4") (pin "2") (pinfunction "P$V-_2") (pintype "bidirectional"))
      (node (ref "U$5") (pin "2") (pinfunction "P$V-_2") (pintype "bidirectional"))
      (node (ref "U1M1") (pin "P18") (pinfunction "GND_P18") (pintype "output"))
      (node (ref "U1M1") (pin "P19") (pinfunction "GND_P19") (pintype "output"))
      (node (ref "U1M1") (pin "P20") (pinfunction "GND_P20") (pintype "output"))
      (node (ref "U1M1") (pin "P26") (pinfunction "GND_P26") (pintype "output"))
      (node (ref "U1M1") (pin "P27") (pinfunction "GND_P27") (pintype "output"))
      (node (ref "U1M1") (pin "P28") (pinfunction "GND_P28") (pintype "output"))
      (node (ref "U1M2") (pin "P18") (pinfunction "GND_P18") (pintype "output"))
      (node (ref "U1M2") (pin "P19") (pinfunction "GND_P19") (pintype "output"))
      (node (ref "U1M2") (pin "P20") (pinfunction "GND_P20") (pintype "output"))
      (node (ref "U1M2") (pin "P26") (pinfunction "GND_P26") (pintype "output"))
      (node (ref "U1M2") (pin "P27") (pinfunction "GND_P27") (pintype "output"))
      (node (ref "U1M2") (pin "P28") (pinfunction "GND_P28") (pintype "output"))
      (node (ref "U1M3") (pin "P18") (pinfunction "GND_P18") (pintype "output"))
      (node (ref "U1M3") (pin "P19") (pinfunction "GND_P19") (pintype "output"))
      (node (ref "U1M3") (pin "P20") (pinfunction "GND_P20") (pintype "output"))
      (node (ref "U1M3") (pin "P26") (pinfunction "GND_P26") (pintype "output"))
      (node (ref "U1M3") (pin "P27") (pinfunction "GND_P27") (pintype "output"))
      (node (ref "U1M3") (pin "P28") (pinfunction "GND_P28") (pintype "output"))
      (node (ref "U1M4") (pin "P18") (pinfunction "GND_P18") (pintype "output"))
      (node (ref "U1M4") (pin "P19") (pinfunction "GND_P19") (pintype "output"))
      (node (ref "U1M4") (pin "P20") (pinfunction "GND_P20") (pintype "output"))
      (node (ref "U1M4") (pin "P26") (pinfunction "GND_P26") (pintype "output"))
      (node (ref "U1M4") (pin "P27") (pinfunction "GND_P27") (pintype "output"))
      (node (ref "U1M4") (pin "P28") (pinfunction "GND_P28") (pintype "output"))
    )
    (net (code "26") (name "INBM1") (class "Default")
      (node (ref "R6M1") (pin "2") (pinfunction "2_2") (pintype "passive"))
      (node (ref "U$4") (pin "6") (pinfunction "Y_6") (pintype "bidirectional"))
    )
    (net (code "27") (name "INBM2") (class "Default")
      (node (ref "R6M2") (pin "2") (pinfunction "2_2") (pintype "passive"))
      (node (ref "U$4") (pin "4") (pinfunction "Y_4") (pintype "bidirectional"))
    )
    (net (code "28") (name "INBM3") (class "Default")
      (node (ref "R6M3") (pin "2") (pinfunction "2_2") (pintype "passive"))
      (node (ref "U$5") (pin "6") (pinfunction "Y_6") (pintype "bidirectional"))
    )
    (net (code "29") (name "INBM4") (class "Default")
      (node (ref "R6M4") (pin "2") (pinfunction "2_2") (pintype "passive"))
      (node (ref "U$5") (pin "4") (pinfunction "Y_4") (pintype "bidirectional"))
    )
    (net (code "30") (name "INM1") (class "Default")
      (node (ref "R5M1") (pin "1") (pinfunction "1_1") (pintype "passive"))
      (node (ref "U$4") (pin "1") (pinfunction "A_1") (pintype "bidirectional"))
      (node (ref "X1") (pin "8") (pinfunction "8_8") (pintype "passive"))
    )
    (net (code "31") (name "INM2") (class "Default")
      (node (ref "R5M2") (pin "1") (pinfunction "1_1") (pintype "passive"))
      (node (ref "U$4") (pin "3") (pinfunction "A_3") (pintype "bidirectional"))
      (node (ref "X1") (pin "6") (pinfunction "6_6") (pintype "passive"))
    )
    (net (code "32") (name "INM3") (class "Default")
      (node (ref "R5M3") (pin "1") (pinfunction "1_1") (pintype "passive"))
      (node (ref "U$5") (pin "1") (pinfunction "A_1") (pintype "bidirectional"))
      (node (ref "X1") (pin "4") (pinfunction "4_4") (pintype "passive"))
    )
    (net (code "33") (name "INM4") (class "Default")
      (node (ref "R5M4") (pin "1") (pinfunction "1_1") (pintype "passive"))
      (node (ref "U$5") (pin "3") (pinfunction "A_3") (pintype "bidirectional"))
      (node (ref "X1") (pin "2") (pinfunction "2_2") (pintype "passive"))
    )
    (net (code "34") (name "L3>L1") (class "Default")
      (node (ref "J7") (pin "P$1") (pinfunction "1_P$1") (pintype "passive"))
      (node (ref "U$21") (pin "P$1") (pinfunction "1_P$1") (pintype "passive"))
      (node (ref "U$26") (pin "+") (pinfunction "P$V+_+") (pintype "bidirectional"))
    )
    (net (code "35") (name "LIGHT_INT") (class "Default")
      (node (ref "1U4") (pin "32") (pinfunction "PA11/USART1_CTS/CAN_RX/TIM1_CH4/USBDM_32") (pintype "bidirectional"))
      (node (ref "J2") (pin "1") (pinfunction "1_1") (pintype "passive"))
    )
    (net (code "36") (name "LSOUT1") (class "Default")
      (node (ref "1C2") (pin "1") (pinfunction "1_1") (pintype "passive"))
      (node (ref "1R3") (pin "2") (pinfunction "2_2") (pintype "passive"))
      (node (ref "1U1") (pin "1") (pinfunction "COM_1") (pintype "bidirectional"))
      (node (ref "1U4") (pin "18") (pinfunction "PB0/ADC12_IN8/TIM3_CH3_18") (pintype "bidirectional"))
    )
    (net (code "37") (name "LSOUT2") (class "Default")
      (node (ref "1C4") (pin "1") (pinfunction "1_1") (pintype "passive"))
      (node (ref "1R5") (pin "2") (pinfunction "2_2") (pintype "passive"))
      (node (ref "1U2") (pin "1") (pinfunction "COM_1") (pintype "bidirectional"))
      (node (ref "1U4") (pin "11") (pinfunction "PA1/USART2_RTS/ADC12_IN1/TIM2_CH2_11") (pintype "bidirectional"))
    )
    (net (code "38") (name "LSOUT3") (class "Default")
      (node (ref "1U3") (pin "1") (pinfunction "COM_1") (pintype "bidirectional"))
      (node (ref "1U4") (pin "10") (pinfunction "PA0_WKUP/USART2_CTS/ADC12_IN0/TIM2_CH1_ETR_10") (pintype "bidirectional"))
    )
    (net (code "39") (name "M1+2") (class "Default")
      (node (ref "J5") (pin "P$1") (pinfunction "1_P$1") (pintype "passive"))
      (node (ref "Q1M1") (pin "3") (pinfunction "S_3") (pintype "bidirectional"))
      (node (ref "Q1M2") (pin "3") (pinfunction "S_3") (pintype "bidirectional"))
      (node (ref "U1M1") (pin "P12") (pinfunction "VBAT_P12") (pintype "power_in"))
      (node (ref "U1M2") (pin "P12") (pinfunction "VBAT_P12") (pintype "power_in"))
    )
    (net (code "40") (name "MOTOR_SW") (class "Default")
      (node (ref "J10") (pin "P$1") (pinfunction "1_P$1") (pintype "passive"))
      (node (ref "J11") (pin "P$1") (pinfunction "1_P$1") (pintype "passive"))
      (node (ref "J20") (pin "P$1") (pinfunction "1_P$1") (pintype "passive"))
      (node (ref "J8") (pin "P$1") (pinfunction "1_P$1") (pintype "passive"))
      (node (ref "J9") (pin "P$1") (pinfunction "1_P$1") (pintype "passive"))
      (node (ref "R1") (pin "2") (pinfunction "2_2") (pintype "passive"))
    )
    (net (code "41") (name "MOUSE_MISO") (class "Default")
      (node (ref "1U4") (pin "16") (pinfunction "PA6/SPI1_MISO/ADC12_IN6/TIM3_CH1_16") (pintype "bidirectional"))
      (node (ref "MOUSE") (pin "7") (pinfunction "7_7") (pintype "passive"))
    )
    (net (code "42") (name "MOUSE_MOSI") (class "Default")
      (node (ref "1U4") (pin "17") (pinfunction "PA7/SPI1_MOSI/ADC12_IN7/TIM3_CH2_17") (pintype "bidirectional"))
      (node (ref "MOUSE") (pin "8") (pinfunction "8_8") (pintype "passive"))
    )
    (net (code "43") (name "MOUSE_MOT") (class "Default")
      (node (ref "1U4") (pin "45") (pinfunction "PB8/TIM4_CH3_45") (pintype "bidirectional"))
      (node (ref "MOUSE") (pin "4") (pinfunction "4_4") (pintype "passive"))
    )
    (net (code "44") (name "MOUSE_RST") (class "Default")
      (node (ref "1U4") (pin "46") (pinfunction "PB9/TIM4_CH4_46") (pintype "input"))
      (node (ref "MOUSE") (pin "3") (pinfunction "3_3") (pintype "passive"))
    )
    (net (code "45") (name "MOUSE_SCK") (class "Default")
      (node (ref "1U4") (pin "15") (pinfunction "PA5/SPI1_SCK/ADC12_IN5_15") (pintype "bidirectional"))
      (node (ref "MOUSE") (pin "6") (pinfunction "6_6") (pintype "passive"))
    )
    (net (code "46") (name "MOUSE_SS") (class "Default")
      (node (ref "1U4") (pin "14") (pinfunction "PA4/SPI1_NSS/USART2_CK/ADC12_IN4_14") (pintype "bidirectional"))
      (node (ref "MOUSE") (pin "5") (pinfunction "5_5") (pintype "passive"))
    )
    (net (code "47") (name "Net-(1D0-PadA)") (class "Default")
      (node (ref "1D0") (pin "A") (pinfunction "A_A") (pintype "passive"))
      (node (ref "1R8") (pin "1") (pinfunction "1_1") (pintype "passive"))
    )
    (net (code "48") (name "Net-(1PT1-E1)") (class "Default")
      (node (ref "1PT1") (pin "E") (pinfunction "E1_E") (pintype "passive"))
      (node (ref "1U2") (pin "5") (pinfunction "CHAN4_5") (pintype "bidirectional"))
    )
    (net (code "49") (name "Net-(1PT2-E1)") (class "Default")
      (node (ref "1PT2") (pin "E") (pinfunction "E1_E") (pintype "passive"))
      (node (ref "1U2") (pin "6") (pinfunction "CHAN3_6") (pintype "bidirectional"))
    )
    (net (code "50") (name "Net-(1PT3-E1)") (class "Default")
      (node (ref "1PT3") (pin "E") (pinfunction "E1_E") (pintype "passive"))
      (node (ref "1U2") (pin "7") (pinfunction "CHAN2_7") (pintype "bidirectional"))
    )
    (net (code "51") (name "Net-(1PT4-E1)") (class "Default")
      (node (ref "1PT4") (pin "E") (pinfunction "E1_E") (pintype "passive"))
      (node (ref "1U2") (pin "8") (pinfunction "CHAN1_8") (pintype "bidirectional"))
    )
    (net (code "52") (name "Net-(1PT5-E1)") (class "Default")
      (node (ref "1PT5") (pin "E") (pinfunction "E1_E") (pintype "passive"))
      (node (ref "1U2") (pin "9") (pinfunction "CHAN0_9") (pintype "bidirectional"))
    )
    (net (code "53") (name "Net-(1PT6-E1)") (class "Default")
      (node (ref "1PT6") (pin "E") (pinfunction "E1_E") (pintype "passive"))
      (node (ref "1U1") (pin "16") (pinfunction "CHAN15_16") (pintype "bidirectional"))
    )
    (net (code "54") (name "Net-(1PT7-E1)") (class "Default")
      (node (ref "1PT7") (pin "E") (pinfunction "E1_E") (pintype "passive"))
      (node (ref "1U1") (pin "17") (pinfunction "CHAN14_17") (pintype "bidirectional"))
    )
    (net (code "55") (name "Net-(1PT8-E1)") (class "Default")
      (node (ref "1PT8") (pin "E") (pinfunction "E1_E") (pintype "passive"))
      (node (ref "1U1") (pin "18") (pinfunction "CHAN13_18") (pintype "bidirectional"))
    )
    (net (code "56") (name "Net-(1PT9-E1)") (class "Default")
      (node (ref "1PT9") (pin "E") (pinfunction "E1_E") (pintype "passive"))
      (node (ref "1U1") (pin "19") (pinfunction "CHAN12_19") (pintype "bidirectional"))
    )
    (net (code "57") (name "Net-(1PT10-E1)") (class "Default")
      (node (ref "1PT10") (pin "E") (pinfunction "E1_E") (pintype "passive"))
      (node (ref "1U1") (pin "20") (pinfunction "CHAN11_20") (pintype "bidirectional"))
    )
    (net (code "58") (name "Net-(1PT11-E1)") (class "Default")
      (node (ref "1PT11") (pin "E") (pinfunction "E1_E") (pintype "passive"))
      (node (ref "1U1") (pin "21") (pinfunction "CHAN10_21") (pintype "bidirectional"))
    )
    (net (code "59") (name "Net-(1PT12-E1)") (class "Default")
      (node (ref "1PT12") (pin "E") (pinfunction "E1_E") (pintype "passive"))
      (node (ref "1U1") (pin "22") (pinfunction "CHAN9_22") (pintype "bidirectional"))
    )
    (net (code "60") (name "Net-(1PT13-E1)") (class "Default")
      (node (ref "1PT13") (pin "E") (pinfunction "E1_E") (pintype "passive"))
      (node (ref "1U1") (pin "23") (pinfunction "CHAN8_23") (pintype "bidirectional"))
    )
    (net (code "61") (name "Net-(1PT14-E1)") (class "Default")
      (node (ref "1PT14") (pin "E") (pinfunction "E1_E") (pintype "passive"))
      (node (ref "1U1") (pin "2") (pinfunction "CHAN7_2") (pintype "bidirectional"))
    )
    (net (code "62") (name "Net-(1PT15-E1)") (class "Default")
      (node (ref "1PT15") (pin "E") (pinfunction "E1_E") (pintype "passive"))
      (node (ref "1U1") (pin "3") (pinfunction "CHAN6_3") (pintype "bidirectional"))
    )
    (net (code "63") (name "Net-(1PT16-E1)") (class "Default")
      (node (ref "1PT16") (pin "E") (pinfunction "E1_E") (pintype "passive"))
      (node (ref "1U1") (pin "4") (pinfunction "CHAN5_4") (pintype "bidirectional"))
    )
    (net (code "64") (name "Net-(1PT17-E1)") (class "Default")
      (node (ref "1PT17") (pin "E") (pinfunction "E1_E") (pintype "passive"))
      (node (ref "1U1") (pin "5") (pinfunction "CHAN4_5") (pintype "bidirectional"))
    )
    (net (code "65") (name "Net-(1PT18-E1)") (class "Default")
      (node (ref "1PT18") (pin "E") (pinfunction "E1_E") (pintype "passive"))
      (node (ref "1U1") (pin "6") (pinfunction "CHAN3_6") (pintype "bidirectional"))
    )
    (net (code "66") (name "Net-(1PT19-E1)") (class "Default")
      (node (ref "1PT19") (pin "E") (pinfunction "E1_E") (pintype "passive"))
      (node (ref "1U1") (pin "7") (pinfunction "CHAN2_7") (pintype "bidirectional"))
    )
    (net (code "67") (name "Net-(1PT20-E1)") (class "Default")
      (node (ref "1PT20") (pin "E") (pinfunction "E1_E") (pintype "passive"))
      (node (ref "1U1") (pin "8") (pinfunction "CHAN1_8") (pintype "bidirectional"))
    )
    (net (code "68") (name "Net-(1PT21-E1)") (class "Default")
      (node (ref "1PT21") (pin "E") (pinfunction "E1_E") (pintype "passive"))
      (node (ref "1U1") (pin "9") (pinfunction "CHAN0_9") (pintype "bidirectional"))
    )
    (net (code "69") (name "Net-(1PT26-E1)") (class "Default")
      (node (ref "1PT26") (pin "E") (pinfunction "E1_E") (pintype "passive"))
      (node (ref "1U2") (pin "16") (pinfunction "CHAN15_16") (pintype "bidirectional"))
    )
    (net (code "70") (name "Net-(1PT27-E1)") (class "Default")
      (node (ref "1PT27") (pin "E") (pinfunction "E1_E") (pintype "passive"))
      (node (ref "1U2") (pin "17") (pinfunction "CHAN14_17") (pintype "bidirectional"))
    )
    (net (code "71") (name "Net-(1PT28-E1)") (class "Default")
      (node (ref "1PT28") (pin "E") (pinfunction "E1_E") (pintype "passive"))
      (node (ref "1U2") (pin "18") (pinfunction "CHAN13_18") (pintype "bidirectional"))
    )
    (net (code "72") (name "Net-(1PT29-E1)") (class "Default")
      (node (ref "1PT29") (pin "E") (pinfunction "E1_E") (pintype "passive"))
      (node (ref "1U2") (pin "19") (pinfunction "CHAN12_19") (pintype "bidirectional"))
    )
    (net (code "73") (name "Net-(1PT30-E1)") (class "Default")
      (node (ref "1PT30") (pin "E") (pinfunction "E1_E") (pintype "passive"))
      (node (ref "1U2") (pin "20") (pinfunction "CHAN11_20") (pintype "bidirectional"))
    )
    (net (code "74") (name "Net-(1PT31-E1)") (class "Default")
      (node (ref "1PT31") (pin "E") (pinfunction "E1_E") (pintype "passive"))
      (node (ref "1U2") (pin "21") (pinfunction "CHAN10_21") (pintype "bidirectional"))
    )
    (net (code "75") (name "Net-(1PT32-E1)") (class "Default")
      (node (ref "1PT32") (pin "E") (pinfunction "E1_E") (pintype "passive"))
      (node (ref "1U2") (pin "22") (pinfunction "CHAN9_22") (pintype "bidirectional"))
    )
    (net (code "76") (name "Net-(1PT33-E1)") (class "Default")
      (node (ref "1PT33") (pin "E") (pinfunction "E1_E") (pintype "passive"))
      (node (ref "1U2") (pin "23") (pinfunction "CHAN8_23") (pintype "bidirectional"))
    )
    (net (code "77") (name "Net-(1PT34-E1)") (class "Default")
      (node (ref "1PT34") (pin "E") (pinfunction "E1_E") (pintype "passive"))
      (node (ref "1U2") (pin "2") (pinfunction "CHAN7_2") (pintype "bidirectional"))
    )
    (net (code "78") (name "Net-(1PT35-E1)") (class "Default")
      (node (ref "1PT35") (pin "E") (pinfunction "E1_E") (pintype "passive"))
      (node (ref "1U2") (pin "3") (pinfunction "CHAN6_3") (pintype "bidirectional"))
    )
    (net (code "79") (name "Net-(1PT36-E1)") (class "Default")
      (node (ref "1PT36") (pin "E") (pinfunction "E1_E") (pintype "passive"))
      (node (ref "1U2") (pin "4") (pinfunction "CHAN5_4") (pintype "bidirectional"))
    )
    (net (code "80") (name "Net-(1SW1-1)") (class "Default")
      (node (ref "1R10") (pin "2") (pinfunction "2_2") (pintype "passive"))
      (node (ref "1SW1") (pin "P$1") (pinfunction "1_P$1") (pintype "passive"))
    )
    (net (code "81") (name "Net-(1U1-EN)") (class "Default")
      (node (ref "1R2") (pin "2") (pinfunction "2_2") (pintype "passive"))
      (node (ref "1U1") (pin "15") (pinfunction "EN_15") (pintype "input"))
    )
    (net (code "82") (name "Net-(1U2-EN)") (class "Default")
      (node (ref "1R4") (pin "2") (pinfunction "2_2") (pintype "passive"))
      (node (ref "1U2") (pin "15") (pinfunction "EN_15") (pintype "input"))
    )
    (net (code "83") (name "Net-(1U3-EN)") (class "Default")
      (node (ref "1R6") (pin "2") (pinfunction "2_2") (pintype "passive"))
      (node (ref "1U3") (pin "15") (pinfunction "EN_15") (pintype "input"))
    )
    (net (code "84") (name "Net-(1U4-BOOT0)") (class "Default")
      (node (ref "1R11") (pin "1") (pinfunction "1_1") (pintype "passive"))
      (node (ref "1U4") (pin "44") (pinfunction "BOOT0_44") (pintype "input"))
    )
    (net (code "85") (name "Net-(2L1-1)") (class "Default")
      (node (ref "2C3") (pin "2") (pinfunction "2_2") (pintype "passive"))
      (node (ref "2D1") (pin "C") (pinfunction "C_C") (pintype "passive"))
      (node (ref "2L1") (pin "P1") (pinfunction "1_P1") (pintype "passive"))
      (node (ref "2U1") (pin "8") (pinfunction "PH_8") (pintype "bidirectional"))
    )
    (net (code "86") (name "Net-(2U1-BOOT)") (class "Default")
      (node (ref "2C3") (pin "1") (pinfunction "1_1") (pintype "passive"))
      (node (ref "2U1") (pin "1") (pinfunction "BOOT_1") (pintype "bidirectional"))
    )
    (net (code "87") (name "Net-(2U1-VSNS)") (class "Default")
      (node (ref "2R1") (pin "1") (pinfunction "1_1") (pintype "passive"))
      (node (ref "2R2") (pin "2") (pinfunction "2_2") (pintype "passive"))
      (node (ref "2U1") (pin "4") (pinfunction "VSNS_4") (pintype "input"))
    )
    (net (code "88") (name "Net-(3C2-Pad1)") (class "Default")
      (node (ref "3C2") (pin "1") (pinfunction "1_1") (pintype "passive"))
      (node (ref "3R1") (pin "1") (pinfunction "1_1") (pintype "passive"))
    )
    (net (code "89") (name "Net-(3C7-Pad1)") (class "Default")
      (node (ref "3C7") (pin "1") (pinfunction "1_1") (pintype "passive"))
      (node (ref "3R10") (pin "1") (pinfunction "1_1") (pintype "passive"))
    )
    (net (code "90") (name "Net-(3D4-PadC)") (class "Default")
      (node (ref "3D4") (pin "C") (pinfunction "C_C") (pintype "passive"))
      (node (ref "3D5") (pin "C") (pinfunction "C_C") (pintype "passive"))
    )
    (net (code "91") (name "Net-(3POT1-CW)") (class "Default")
      (node (ref "3POT1") (pin "3") (pinfunction "CW_3") (pintype "passive"))
      (node (ref "3R4") (pin "1") (pinfunction "1_1") (pintype "passive"))
    )
    (net (code "92") (name "Net-(3Q3-D)") (class "Default")
      (node (ref "3D5") (pin "A") (pinfunction "A_A") (pintype "passive"))
      (node (ref "3Q3") (pin "2") (pinfunction "D_2") (pintype "bidirectional"))
      (node (ref "3R10") (pin "2") (pinfunction "2_2") (pintype "passive"))
      (node (ref "J1") (pin "-") (pinfunction "P$V-_-") (pintype "bidirectional"))
    )
    (net (code "93") (name "Net-(3Q3-G)") (class "Default")
      (node (ref "3Q3") (pin "1") (pinfunction "G_1") (pintype "bidirectional"))
      (node (ref "3R7") (pin "2") (pinfunction "2_2") (pintype "passive"))
    )
    (net (code "94") (name "Net-(3Q3-S)") (class "Default")
      (node (ref "3C7") (pin "2") (pinfunction "2_2") (pintype "passive"))
      (node (ref "3Q3") (pin "3") (pinfunction "S_3") (pintype "bidirectional"))
      (node (ref "3Q4") (pin "3") (pinfunction "D_3") (pintype "bidirectional"))
      (node (ref "3R8") (pin "1") (pinfunction "1_1") (pintype "passive"))
    )
    (net (code "95") (name "Net-(3U1-COMP)") (class "Default")
      (node (ref "3R1") (pin "2") (pinfunction "2_2") (pintype "passive"))
      (node (ref "3U1") (pin "P1") (pinfunction "COMP_P1") (pintype "bidirectional"))
    )
    (net (code "96") (name "Net-(3U1-SW)") (class "Default")
      (node (ref "3D1") (pin "A") (pinfunction "A_A") (pintype "passive"))
      (node (ref "3L1") (pin "2") (pinfunction "2_2") (pintype "passive"))
      (node (ref "3U1") (pin "P4") (pinfunction "SW_P4") (pintype "output"))
    )
    (net (code "97") (name "Net-(D1M1-PadC)") (class "Default")
      (node (ref "D1M1") (pin "C") (pinfunction "C_C") (pintype "passive"))
      (node (ref "D2M1") (pin "A") (pinfunction "A_A") (pintype "passive"))
      (node (ref "R12M1") (pin "1") (pinfunction "1_1") (pintype "passive"))
    )
    (net (code "98") (name "Net-(D1M2-PadC)") (class "Default")
      (node (ref "D1M2") (pin "C") (pinfunction "C_C") (pintype "passive"))
      (node (ref "D2M2") (pin "A") (pinfunction "A_A") (pintype "passive"))
      (node (ref "R12M2") (pin "1") (pinfunction "1_1") (pintype "passive"))
    )
    (net (code "99") (name "Net-(D1M3-PadC)") (class "Default")
      (node (ref "D1M3") (pin "C") (pinfunction "C_C") (pintype "passive"))
      (node (ref "D2M3") (pin "A") (pinfunction "A_A") (pintype "passive"))
      (node (ref "R12M3") (pin "1") (pinfunction "1_1") (pintype "passive"))
    )
    (net (code "100") (name "Net-(D1M4-PadC)") (class "Default")
      (node (ref "D1M4") (pin "C") (pinfunction "C_C") (pintype "passive"))
      (node (ref "D2M4") (pin "A") (pinfunction "A_A") (pintype "passive"))
      (node (ref "R12M4") (pin "1") (pinfunction "1_1") (pintype "passive"))
    )
    (net (code "101") (name "Net-(J3-1)") (class "Default")
      (node (ref "J3") (pin "P$1") (pinfunction "1_P$1") (pintype "passive"))
      (node (ref "Q1M4") (pin "3") (pinfunction "S_3") (pintype "bidirectional"))
      (node (ref "U1M4") (pin "P12") (pinfunction "VBAT_P12") (pintype "power_in"))
    )
    (net (code "102") (name "Net-(J4-1)") (class "Default")
      (node (ref "J4") (pin "P$1") (pinfunction "1_P$1") (pintype "passive"))
      (node (ref "Q1M3") (pin "3") (pinfunction "S_3") (pintype "bidirectional"))
      (node (ref "U1M3") (pin "P12") (pinfunction "VBAT_P12") (pintype "power_in"))
    )
    (net (code "103") (name "Net-(Q1M1-D)") (class "Default")
      (node (ref "C2M1") (pin "+") (pinfunction "+_+") (pintype "passive"))
      (node (ref "C3M1") (pin "1") (pinfunction "1_1") (pintype "passive"))
      (node (ref "Q1M1") (pin "4") (pinfunction "D_4") (pintype "bidirectional"))
      (node (ref "U1M1") (pin "P$19") (pinfunction "VCC_P$19") (pintype "power_in"))
      (node (ref "U1M1") (pin "P$20") (pinfunction "VCC_P$20") (pintype "power_in"))
      (node (ref "U1M1") (pin "P$21") (pinfunction "VCC_P$21") (pintype "power_in"))
      (node (ref "U1M1") (pin "P$22") (pinfunction "VCC_P$22") (pintype "power_in"))
      (node (ref "U1M1") (pin "P$23") (pinfunction "VCC_P$23") (pintype "power_in"))
      (node (ref "U1M1") (pin "P$24") (pinfunction "VCC_P$24") (pintype "power_in"))
      (node (ref "U1M1") (pin "P$25") (pinfunction "VCC_P$25") (pintype "power_in"))
      (node (ref "U1M1") (pin "P$26") (pinfunction "VCC_P$26") (pintype "power_in"))
      (node (ref "U1M1") (pin "P$27") (pinfunction "VCC_P$27") (pintype "power_in"))
      (node (ref "U1M1") (pin "P$28") (pinfunction "VCC_P$28") (pintype "power_in"))
      (node (ref "U1M1") (pin "P13") (pinfunction "VCC_P13") (pintype "power_in"))
      (node (ref "U1M1") (pin "P23") (pinfunction "VCC_P23") (pintype "power_in"))
      (node (ref "U1M1") (pin "P3") (pinfunction "VCC_P3") (pintype "power_in"))
      (node (ref "U1M1") (pin "SLUG1") (pinfunction "VCC_SLUG1") (pintype "power_in"))
    )
    (net (code "104") (name "Net-(Q1M2-D)") (class "Default")
      (node (ref "C2M2") (pin "+") (pinfunction "+_+") (pintype "passive"))
      (node (ref "C3M2") (pin "1") (pinfunction "1_1") (pintype "passive"))
      (node (ref "Q1M2") (pin "4") (pinfunction "D_4") (pintype "bidirectional"))
      (node (ref "U1M2") (pin "P$19") (pinfunction "VCC_P$19") (pintype "power_in"))
      (node (ref "U1M2") (pin "P$20") (pinfunction "VCC_P$20") (pintype "power_in"))
      (node (ref "U1M2") (pin "P$21") (pinfunction "VCC_P$21") (pintype "power_in"))
      (node (ref "U1M2") (pin "P$22") (pinfunction "VCC_P$22") (pintype "power_in"))
      (node (ref "U1M2") (pin "P$23") (pinfunction "VCC_P$23") (pintype "power_in"))
      (node (ref "U1M2") (pin "P$24") (pinfunction "VCC_P$24") (pintype "power_in"))
      (node (ref "U1M2") (pin "P$25") (pinfunction "VCC_P$25") (pintype "power_in"))
      (node (ref "U1M2") (pin "P$26") (pinfunction "VCC_P$26") (pintype "power_in"))
      (node (ref "U1M2") (pin "P$27") (pinfunction "VCC_P$27") (pintype "power_in"))
      (node (ref "U1M2") (pin "P$28") (pinfunction "VCC_P$28") (pintype "power_in"))
      (node (ref "U1M2") (pin "P13") (pinfunction "VCC_P13") (pintype "power_in"))
      (node (ref "U1M2") (pin "P23") (pinfunction "VCC_P23") (pintype "power_in"))
      (node (ref "U1M2") (pin "P3") (pinfunction "VCC_P3") (pintype "power_in"))
      (node (ref "U1M2") (pin "SLUG1") (pinfunction "VCC_SLUG1") (pintype "power_in"))
    )
    (net (code "105") (name "Net-(Q1M3-D)") (class "Default")
      (node (ref "C2M3") (pin "+") (pinfunction "+_+") (pintype "passive"))
      (node (ref "C3M3") (pin "1") (pinfunction "1_1") (pintype "passive"))
      (node (ref "Q1M3") (pin "4") (pinfunction "D_4") (pintype "bidirectional"))
      (node (ref "U1M3") (pin "P$19") (pinfunction "VCC_P$19") (pintype "power_in"))
      (node (ref "U1M3") (pin "P$20") (pinfunction "VCC_P$20") (pintype "power_in"))
      (node (ref "U1M3") (pin "P$21") (pinfunction "VCC_P$21") (pintype "power_in"))
      (node (ref "U1M3") (pin "P$22") (pinfunction "VCC_P$22") (pintype "power_in"))
      (node (ref "U1M3") (pin "P$23") (pinfunction "VCC_P$23") (pintype "power_in"))
      (node (ref "U1M3") (pin "P$24") (pinfunction "VCC_P$24") (pintype "power_in"))
      (node (ref "U1M3") (pin "P$25") (pinfunction "VCC_P$25") (pintype "power_in"))
      (node (ref "U1M3") (pin "P$26") (pinfunction "VCC_P$26") (pintype "power_in"))
      (node (ref "U1M3") (pin "P$27") (pinfunction "VCC_P$27") (pintype "power_in"))
      (node (ref "U1M3") (pin "P$28") (pinfunction "VCC_P$28") (pintype "power_in"))
      (node (ref "U1M3") (pin "P13") (pinfunction "VCC_P13") (pintype "power_in"))
      (node (ref "U1M3") (pin "P23") (pinfunction "VCC_P23") (pintype "power_in"))
      (node (ref "U1M3") (pin "P3") (pinfunction "VCC_P3") (pintype "power_in"))
      (node (ref "U1M3") (pin "SLUG1") (pinfunction "VCC_SLUG1") (pintype "power_in"))
    )
    (net (code "106") (name "Net-(Q1M4-D)") (class "Default")
      (node (ref "C2M4") (pin "+") (pinfunction "+_+") (pintype "passive"))
      (node (ref "C3M4") (pin "1") (pinfunction "1_1") (pintype "passive"))
      (node (ref "Q1M4") (pin "4") (pinfunction "D_4") (pintype "bidirectional"))
      (node (ref "U1M4") (pin "P$19") (pinfunction "VCC_P$19") (pintype "power_in"))
      (node (ref "U1M4") (pin "P$20") (pinfunction "VCC_P$20") (pintype "power_in"))
      (node (ref "U1M4") (pin "P$21") (pinfunction "VCC_P$21") (pintype "power_in"))
      (node (ref "U1M4") (pin "P$22") (pinfunction "VCC_P$22") (pintype "power_in"))
      (node (ref "U1M4") (pin "P$23") (pinfunction "VCC_P$23") (pintype "power_in"))
      (node (ref "U1M4") (pin "P$24") (pinfunction "VCC_P$24") (pintype "power_in"))
      (node (ref "U1M4") (pin "P$25") (pinfunction "VCC_P$25") (pintype "power_in"))
      (node (ref "U1M4") (pin "P$26") (pinfunction "VCC_P$26") (pintype "power_in"))
      (node (ref "U1M4") (pin "P$27") (pinfunction "VCC_P$27") (pintype "power_in"))
      (node (ref "U1M4") (pin "P$28") (pinfunction "VCC_P$28") (pintype "power_in"))
      (node (ref "U1M4") (pin "P13") (pinfunction "VCC_P13") (pintype "power_in"))
      (node (ref "U1M4") (pin "P23") (pinfunction "VCC_P23") (pintype "power_in"))
      (node (ref "U1M4") (pin "P3") (pinfunction "VCC_P3") (pintype "power_in"))
      (node (ref "U1M4") (pin "SLUG1") (pinfunction "VCC_SLUG1") (pintype "power_in"))
    )
    (net (code "107") (name "Net-(U$17-1)") (class "Default")
      (node (ref "1D1") (pin "A") (pinfunction "A_A") (pintype "passive"))
      (node (ref "1D10") (pin "A") (pinfunction "A_A") (pintype "passive"))
      (node (ref "1D11") (pin "A") (pinfunction "A_A") (pintype "passive"))
      (node (ref "1D12") (pin "A") (pinfunction "A_A") (pintype "passive"))
      (node (ref "1D13") (pin "A") (pinfunction "A_A") (pintype "passive"))
      (node (ref "1D14") (pin "A") (pinfunction "A_A") (pintype "passive"))
      (node (ref "1D15") (pin "A") (pinfunction "A_A") (pintype "passive"))
      (node (ref "1D16") (pin "A") (pinfunction "A_A") (pintype "passive"))
      (node (ref "1D17") (pin "A") (pinfunction "A_A") (pintype "passive"))
      (node (ref "1D18") (pin "A") (pinfunction "A_A") (pintype "passive"))
      (node (ref "1D19") (pin "A") (pinfunction "A_A") (pintype "passive"))
      (node (ref "1D2") (pin "A") (pinfunction "A_A") (pintype "passive"))
      (node (ref "1D20") (pin "A") (pinfunction "A_A") (pintype "passive"))
      (node (ref "1D21") (pin "A") (pinfunction "A_A") (pintype "passive"))
      (node (ref "1D22") (pin "A") (pinfunction "A_A") (pintype "passive"))
      (node (ref "1D23") (pin "A") (pinfunction "A_A") (pintype "passive"))
      (node (ref "1D24") (pin "A") (pinfunction "A_A") (pintype "passive"))
      (node (ref "1D25") (pin "A") (pinfunction "A_A") (pintype "passive"))
      (node (ref "1D26") (pin "A") (pinfunction "A_A") (pintype "passive"))
      (node (ref "1D27") (pin "A") (pinfunction "A_A") (pintype "passive"))
      (node (ref "1D28") (pin "A") (pinfunction "A_A") (pintype "passive"))
      (node (ref "1D29") (pin "A") (pinfunction "A_A") (pintype "passive"))
      (node (ref "1D3") (pin "A") (pinfunction "A_A") (pintype "passive"))
      (node (ref "1D30") (pin "A") (pinfunction "A_A") (pintype "passive"))
      (node (ref "1D31") (pin "A") (pinfunction "A_A") (pintype "passive"))
      (node (ref "1D32") (pin "A") (pinfunction "A_A") (pintype "passive"))
      (node (ref "1D33") (pin "A") (pinfunction "A_A") (pintype "passive"))
      (node (ref "1D34") (pin "A") (pinfunction "A_A") (pintype "passive"))
      (node (ref "1D35") (pin "A") (pinfunction "A_A") (pintype "passive"))
      (node (ref "1D36") (pin "A") (pinfunction "A_A") (pintype "passive"))
      (node (ref "1D38") (pin "A") (pinfunction "A_A") (pintype "passive"))
      (node (ref "1D4") (pin "A") (pinfunction "A_A") (pintype "passive"))
      (node (ref "1D40") (pin "A") (pinfunction "A_A") (pintype "passive"))
      (node (ref "1D5") (pin "A") (pinfunction "A_A") (pintype "passive"))
      (node (ref "1D6") (pin "A") (pinfunction "A_A") (pintype "passive"))
      (node (ref "1D7") (pin "A") (pinfunction "A_A") (pintype "passive"))
      (node (ref "1D8") (pin "A") (pinfunction "A_A") (pintype "passive"))
      (node (ref "1D9") (pin "A") (pinfunction "A_A") (pintype "passive"))
      (node (ref "1R1") (pin "1") (pinfunction "1_1") (pintype "passive"))
      (node (ref "C3") (pin "1") (pinfunction "1_1") (pintype "passive"))
      (node (ref "LED1") (pin "1") (pinfunction "1_1") (pintype "passive"))
      (node (ref "LED2") (pin "1") (pinfunction "1_1") (pintype "passive"))
      (node (ref "U$17") (pin "P$1") (pinfunction "1_P$1") (pintype "passive"))
      (node (ref "U$22") (pin "P$1") (pinfunction "1_P$1") (pintype "passive"))
    )
    (net (code "108") (name "Net-(U$27-1)") (class "Default")
      (node (ref "U$27") (pin "P$1") (pinfunction "1_P$1") (pintype "passive"))
      (node (ref "U$30") (pin "2") (pinfunction "P_2") (pintype "passive"))
    )
    (net (code "109") (name "Net-(U$30-S)") (class "Default")
      (node (ref "1R1") (pin "2") (pinfunction "2_2") (pintype "passive"))
      (node (ref "U$30") (pin "3") (pinfunction "S_3") (pintype "passive"))
    )
    (net (code "110") (name "Net-(U1M1-CS)") (class "Default")
      (node (ref "R10M1") (pin "2") (pinfunction "2_2") (pintype "passive"))
      (node (ref "R8M1") (pin "2") (pinfunction "2_2") (pintype "passive"))
      (node (ref "U1M1") (pin "P8") (pinfunction "CS_P8") (pintype "output"))
    )
    (net (code "111") (name "Net-(U1M1-EN_A)") (class "Default")
      (node (ref "R2M1") (pin "1") (pinfunction "1_1") (pintype "passive"))
      (node (ref "U1M1") (pin "P5") (pinfunction "EN_A_P5") (pintype "bidirectional"))
    )
    (net (code "112") (name "Net-(U1M1-EN_B)") (class "Default")
      (node (ref "R1M1") (pin "1") (pinfunction "1_1") (pintype "passive"))
      (node (ref "U1M1") (pin "P9") (pinfunction "EN_B_P9") (pintype "bidirectional"))
    )
    (net (code "113") (name "Net-(U1M1-IN_A)") (class "Default")
      (node (ref "R5M1") (pin "2") (pinfunction "2_2") (pintype "passive"))
      (node (ref "U1M1") (pin "P4") (pinfunction "IN_A_P4") (pintype "input"))
    )
    (net (code "114") (name "Net-(U1M1-IN_B)") (class "Default")
      (node (ref "R6M1") (pin "1") (pinfunction "1_1") (pintype "passive"))
      (node (ref "U1M1") (pin "P10") (pinfunction "IN_B_P10") (pintype "input"))
    )
    (net (code "115") (name "Net-(U1M1-PWM_IN)") (class "Default")
      (node (ref "R7M1") (pin "1") (pinfunction "1_1") (pintype "passive"))
      (node (ref "U1M1") (pin "P7") (pinfunction "PWM_IN_P7") (pintype "input"))
    )
    (net (code "116") (name "Net-(U1M2-CS)") (class "Default")
      (node (ref "R10M2") (pin "2") (pinfunction "2_2") (pintype "passive"))
      (node (ref "R8M2") (pin "2") (pinfunction "2_2") (pintype "passive"))
      (node (ref "U1M2") (pin "P8") (pinfunction "CS_P8") (pintype "output"))
    )
    (net (code "117") (name "Net-(U1M2-EN_A)") (class "Default")
      (node (ref "R2M2") (pin "1") (pinfunction "1_1") (pintype "passive"))
      (node (ref "U1M2") (pin "P5") (pinfunction "EN_A_P5") (pintype "bidirectional"))
    )
    (net (code "118") (name "Net-(U1M2-EN_B)") (class "Default")
      (node (ref "R1M2") (pin "1") (pinfunction "1_1") (pintype "passive"))
      (node (ref "U1M2") (pin "P9") (pinfunction "EN_B_P9") (pintype "bidirectional"))
    )
    (net (code "119") (name "Net-(U1M2-IN_A)") (class "Default")
      (node (ref "R5M2") (pin "2") (pinfunction "2_2") (pintype "passive"))
      (node (ref "U1M2") (pin "P4") (pinfunction "IN_A_P4") (pintype "input"))
    )
    (net (code "120") (name "Net-(U1M2-IN_B)") (class "Default")
      (node (ref "R6M2") (pin "1") (pinfunction "1_1") (pintype "passive"))
      (node (ref "U1M2") (pin "P10") (pinfunction "IN_B_P10") (pintype "input"))
    )
    (net (code "121") (name "Net-(U1M2-PWM_IN)") (class "Default")
      (node (ref "R7M2") (pin "1") (pinfunction "1_1") (pintype "passive"))
      (node (ref "U1M2") (pin "P7") (pinfunction "PWM_IN_P7") (pintype "input"))
    )
    (net (code "122") (name "Net-(U1M3-CS)") (class "Default")
      (node (ref "R10M3") (pin "2") (pinfunction "2_2") (pintype "passive"))
      (node (ref "R8M3") (pin "2") (pinfunction "2_2") (pintype "passive"))
      (node (ref "U1M3") (pin "P8") (pinfunction "CS_P8") (pintype "output"))
    )
    (net (code "123") (name "Net-(U1M3-EN_A)") (class "Default")
      (node (ref "R2M3") (pin "1") (pinfunction "1_1") (pintype "passive"))
      (node (ref "U1M3") (pin "P5") (pinfunction "EN_A_P5") (pintype "bidirectional"))
    )
    (net (code "124") (name "Net-(U1M3-EN_B)") (class "Default")
      (node (ref "R1M3") (pin "1") (pinfunction "1_1") (pintype "passive"))
      (node (ref "U1M3") (pin "P9") (pinfunction "EN_B_P9") (pintype "bidirectional"))
    )
    (net (code "125") (name "Net-(U1M3-IN_A)") (class "Default")
      (node (ref "R5M3") (pin "2") (pinfunction "2_2") (pintype "passive"))
      (node (ref "U1M3") (pin "P4") (pinfunction "IN_A_P4") (pintype "input"))
    )
    (net (code "126") (name "Net-(U1M3-IN_B)") (class "Default")
      (node (ref "R6M3") (pin "1") (pinfunction "1_1") (pintype "passive"))
      (node (ref "U1M3") (pin "P10") (pinfunction "IN_B_P10") (pintype "input"))
    )
    (net (code "127") (name "Net-(U1M3-PWM_IN)") (class "Default")
      (node (ref "R7M3") (pin "1") (pinfunction "1_1") (pintype "passive"))
      (node (ref "U1M3") (pin "P7") (pinfunction "PWM_IN_P7") (pintype "input"))
    )
    (net (code "128") (name "Net-(U1M4-CS)") (class "Default")
      (node (ref "R10M4") (pin "2") (pinfunction "2_2") (pintype "passive"))
      (node (ref "R8M4") (pin "2") (pinfunction "2_2") (pintype "passive"))
      (node (ref "U1M4") (pin "P8") (pinfunction "CS_P8") (pintype "output"))
    )
    (net (code "129") (name "Net-(U1M4-EN_A)") (class "Default")
      (node (ref "R2M4") (pin "1") (pinfunction "1_1") (pintype "passive"))
      (node (ref "U1M4") (pin "P5") (pinfunction "EN_A_P5") (pintype "bidirectional"))
    )
    (net (code "130") (name "Net-(U1M4-EN_B)") (class "Default")
      (node (ref "R1M4") (pin "1") (pinfunction "1_1") (pintype "passive"))
      (node (ref "U1M4") (pin "P9") (pinfunction "EN_B_P9") (pintype "bidirectional"))
    )
    (net (code "131") (name "Net-(U1M4-IN_A)") (class "Default")
      (node (ref "R5M4") (pin "2") (pinfunction "2_2") (pintype "passive"))
      (node (ref "U1M4") (pin "P4") (pinfunction "IN_A_P4") (pintype "input"))
    )
    (net (code "132") (name "Net-(U1M4-IN_B)") (class "Default")
      (node (ref "R6M4") (pin "1") (pinfunction "1_1") (pintype "passive"))
      (node (ref "U1M4") (pin "P10") (pinfunction "IN_B_P10") (pintype "input"))
    )
    (net (code "133") (name "Net-(U1M4-PWM_IN)") (class "Default")
      (node (ref "R7M4") (pin "1") (pinfunction "1_1") (pintype "passive"))
      (node (ref "U1M4") (pin "P7") (pinfunction "PWM_IN_P7") (pintype "input"))
    )
    (net (code "134") (name "OSC_IN") (class "Default")
      (node (ref "1C9") (pin "1") (pinfunction "1_1") (pintype "passive"))
      (node (ref "1OSC") (pin "P$2") (pinfunction "2_P$2") (pintype "passive"))
      (node (ref "1U4") (pin "5") (pinfunction "PD0-OSC_IN_5") (pintype "input"))
    )
    (net (code "135") (name "OSC_OUT") (class "Default")
      (node (ref "1C10") (pin "1") (pinfunction "1_1") (pintype "passive"))
      (node (ref "1OSC") (pin "P$1") (pinfunction "1_P$1") (pintype "passive"))
      (node (ref "1U4") (pin "6") (pinfunction "PD1-OSC_OUT_6") (pintype "input"))
    )
    (net (code "136") (name "OUTAM1") (class "Default")
      (node (ref "CONN_M1") (pin "+") (pinfunction "P$V+_+") (pintype "bidirectional"))
      (node (ref "D1M1") (pin "A") (pinfunction "A_A") (pintype "passive"))
      (node (ref "D2M1") (pin "C") (pinfunction "C_C") (pintype "passive"))
      (node (ref "U1M1") (pin "P$1") (pinfunction "OUT_A_P$1") (pintype "output"))
      (node (ref "U1M1") (pin "P$2") (pinfunction "OUT_A_P$2") (pintype "output"))
      (node (ref "U1M1") (pin "P$3") (pinfunction "OUT_A_P$3") (pintype "output"))
      (node (ref "U1M1") (pin "P$4") (pinfunction "OUT_A_P$4") (pintype "output"))
      (node (ref "U1M1") (pin "P$5") (pinfunction "OUT_A_P$5") (pintype "output"))
      (node (ref "U1M1") (pin "P$6") (pinfunction "OUT_A_P$6") (pintype "output"))
      (node (ref "U1M1") (pin "P$7") (pinfunction "OUT_A_P$7") (pintype "output"))
      (node (ref "U1M1") (pin "P$8") (pinfunction "OUT_A_P$8") (pintype "output"))
      (node (ref "U1M1") (pin "P$9") (pinfunction "OUT_A_P$9") (pintype "output"))
      (node (ref "U1M1") (pin "P1") (pinfunction "OUT_A_P1") (pintype "output"))
      (node (ref "U1M1") (pin "P25") (pinfunction "OUT_A_P25") (pintype "output"))
      (node (ref "U1M1") (pin "P30") (pinfunction "OUT_A_P30") (pintype "output"))
      (node (ref "U1M1") (pin "SLUG2") (pinfunction "OUT_A_SLUG2") (pintype "output"))
    )
    (net (code "137") (name "OUTAM2") (class "Default")
      (node (ref "CONN_M2") (pin "+") (pinfunction "P$V+_+") (pintype "bidirectional"))
      (node (ref "D1M2") (pin "A") (pinfunction "A_A") (pintype "passive"))
      (node (ref "D2M2") (pin "C") (pinfunction "C_C") (pintype "passive"))
      (node (ref "U1M2") (pin "P$1") (pinfunction "OUT_A_P$1") (pintype "output"))
      (node (ref "U1M2") (pin "P$2") (pinfunction "OUT_A_P$2") (pintype "output"))
      (node (ref "U1M2") (pin "P$3") (pinfunction "OUT_A_P$3") (pintype "output"))
      (node (ref "U1M2") (pin "P$4") (pinfunction "OUT_A_P$4") (pintype "output"))
      (node (ref "U1M2") (pin "P$5") (pinfunction "OUT_A_P$5") (pintype "output"))
      (node (ref "U1M2") (pin "P$6") (pinfunction "OUT_A_P$6") (pintype "output"))
      (node (ref "U1M2") (pin "P$7") (pinfunction "OUT_A_P$7") (pintype "output"))
      (node (ref "U1M2") (pin "P$8") (pinfunction "OUT_A_P$8") (pintype "output"))
      (node (ref "U1M2") (pin "P$9") (pinfunction "OUT_A_P$9") (pintype "output"))
      (node (ref "U1M2") (pin "P1") (pinfunction "OUT_A_P1") (pintype "output"))
      (node (ref "U1M2") (pin "P25") (pinfunction "OUT_A_P25") (pintype "output"))
      (node (ref "U1M2") (pin "P30") (pinfunction "OUT_A_P30") (pintype "output"))
      (node (ref "U1M2") (pin "SLUG2") (pinfunction "OUT_A_SLUG2") (pintype "output"))
    )
    (net (code "138") (name "OUTAM3") (class "Default")
      (node (ref "CONN_M3") (pin "+") (pinfunction "P$V+_+") (pintype "bidirectional"))
      (node (ref "D1M3") (pin "A") (pinfunction "A_A") (pintype "passive"))
      (node (ref "D2M3") (pin "C") (pinfunction "C_C") (pintype "passive"))
      (node (ref "U1M3") (pin "P$1") (pinfunction "OUT_A_P$1") (pintype "output"))
      (node (ref "U1M3") (pin "P$2") (pinfunction "OUT_A_P$2") (pintype "output"))
      (node (ref "U1M3") (pin "P$3") (pinfunction "OUT_A_P$3") (pintype "output"))
      (node (ref "U1M3") (pin "P$4") (pinfunction "OUT_A_P$4") (pintype "output"))
      (node (ref "U1M3") (pin "P$5") (pinfunction "OUT_A_P$5") (pintype "output"))
      (node (ref "U1M3") (pin "P$6") (pinfunction "OUT_A_P$6") (pintype "output"))
      (node (ref "U1M3") (pin "P$7") (pinfunction "OUT_A_P$7") (pintype "output"))
      (node (ref "U1M3") (pin "P$8") (pinfunction "OUT_A_P$8") (pintype "output"))
      (node (ref "U1M3") (pin "P$9") (pinfunction "OUT_A_P$9") (pintype "output"))
      (node (ref "U1M3") (pin "P1") (pinfunction "OUT_A_P1") (pintype "output"))
      (node (ref "U1M3") (pin "P25") (pinfunction "OUT_A_P25") (pintype "output"))
      (node (ref "U1M3") (pin "P30") (pinfunction "OUT_A_P30") (pintype "output"))
      (node (ref "U1M3") (pin "SLUG2") (pinfunction "OUT_A_SLUG2") (pintype "output"))
    )
    (net (code "139") (name "OUTAM4") (class "Default")
      (node (ref "CONN_M4") (pin "+") (pinfunction "P$V+_+") (pintype "bidirectional"))
      (node (ref "D1M4") (pin "A") (pinfunction "A_A") (pintype "passive"))
      (node (ref "D2M4") (pin "C") (pinfunction "C_C") (pintype "passive"))
      (node (ref "U1M4") (pin "P$1") (pinfunction "OUT_A_P$1") (pintype "output"))
      (node (ref "U1M4") (pin "P$2") (pinfunction "OUT_A_P$2") (pintype "output"))
      (node (ref "U1M4") (pin "P$3") (pinfunction "OUT_A_P$3") (pintype "output"))
      (node (ref "U1M4") (pin "P$4") (pinfunction "OUT_A_P$4") (pintype "output"))
      (node (ref "U1M4") (pin "P$5") (pinfunction "OUT_A_P$5") (pintype "output"))
      (node (ref "U1M4") (pin "P$6") (pinfunction "OUT_A_P$6") (pintype "output"))
      (node (ref "U1M4") (pin "P$7") (pinfunction "OUT_A_P$7") (pintype "output"))
      (node (ref "U1M4") (pin "P$8") (pinfunction "OUT_A_P$8") (pintype "output"))
      (node (ref "U1M4") (pin "P$9") (pinfunction "OUT_A_P$9") (pintype "output"))
      (node (ref "U1M4") (pin "P1") (pinfunction "OUT_A_P1") (pintype "output"))
      (node (ref "U1M4") (pin "P25") (pinfunction "OUT_A_P25") (pintype "output"))
      (node (ref "U1M4") (pin "P30") (pinfunction "OUT_A_P30") (pintype "output"))
      (node (ref "U1M4") (pin "SLUG2") (pinfunction "OUT_A_SLUG2") (pintype "output"))
    )
    (net (code "140") (name "OUTBM1") (class "Default")
      (node (ref "CONN_M1") (pin "-") (pinfunction "P$V-_-") (pintype "bidirectional"))
      (node (ref "R12M1") (pin "2") (pinfunction "2_2") (pintype "passive"))
      (node (ref "U1M1") (pin "P$10") (pinfunction "OUT_B_P$10") (pintype "output"))
      (node (ref "U1M1") (pin "P$11") (pinfunction "OUT_B_P$11") (pintype "output"))
      (node (ref "U1M1") (pin "P$12") (pinfunction "OUT_B_P$12") (pintype "output"))
      (node (ref "U1M1") (pin "P$13") (pinfunction "OUT_B_P$13") (pintype "output"))
      (node (ref "U1M1") (pin "P$14") (pinfunction "OUT_B_P$14") (pintype "output"))
      (node (ref "U1M1") (pin "P$15") (pinfunction "OUT_B_P$15") (pintype "output"))
      (node (ref "U1M1") (pin "P$16") (pinfunction "OUT_B_P$16") (pintype "output"))
      (node (ref "U1M1") (pin "P$17") (pinfunction "OUT_B_P$17") (pintype "output"))
      (node (ref "U1M1") (pin "P$18") (pinfunction "OUT_B_P$18") (pintype "output"))
      (node (ref "U1M1") (pin "P15") (pinfunction "OUT_B_P15") (pintype "output"))
      (node (ref "U1M1") (pin "P16") (pinfunction "OUT_B_P16") (pintype "output"))
      (node (ref "U1M1") (pin "P21") (pinfunction "OUT_B_P21") (pintype "output"))
      (node (ref "U1M1") (pin "SLUG3") (pinfunction "OUT_B_SLUG3") (pintype "output"))
    )
    (net (code "141") (name "OUTBM2") (class "Default")
      (node (ref "CONN_M2") (pin "-") (pinfunction "P$V-_-") (pintype "bidirectional"))
      (node (ref "R12M2") (pin "2") (pinfunction "2_2") (pintype "passive"))
      (node (ref "U1M2") (pin "P$10") (pinfunction "OUT_B_P$10") (pintype "output"))
      (node (ref "U1M2") (pin "P$11") (pinfunction "OUT_B_P$11") (pintype "output"))
      (node (ref "U1M2") (pin "P$12") (pinfunction "OUT_B_P$12") (pintype "output"))
      (node (ref "U1M2") (pin "P$13") (pinfunction "OUT_B_P$13") (pintype "output"))
      (node (ref "U1M2") (pin "P$14") (pinfunction "OUT_B_P$14") (pintype "output"))
      (node (ref "U1M2") (pin "P$15") (pinfunction "OUT_B_P$15") (pintype "output"))
      (node (ref "U1M2") (pin "P$16") (pinfunction "OUT_B_P$16") (pintype "output"))
      (node (ref "U1M2") (pin "P$17") (pinfunction "OUT_B_P$17") (pintype "output"))
      (node (ref "U1M2") (pin "P$18") (pinfunction "OUT_B_P$18") (pintype "output"))
      (node (ref "U1M2") (pin "P15") (pinfunction "OUT_B_P15") (pintype "output"))
      (node (ref "U1M2") (pin "P16") (pinfunction "OUT_B_P16") (pintype "output"))
      (node (ref "U1M2") (pin "P21") (pinfunction "OUT_B_P21") (pintype "output"))
      (node (ref "U1M2") (pin "SLUG3") (pinfunction "OUT_B_SLUG3") (pintype "output"))
    )
    (net (code "142") (name "OUTBM3") (class "Default")
      (node (ref "CONN_M3") (pin "-") (pinfunction "P$V-_-") (pintype "bidirectional"))
      (node (ref "R12M3") (pin "2") (pinfunction "2_2") (pintype "passive"))
      (node (ref "U1M3") (pin "P$10") (pinfunction "OUT_B_P$10") (pintype "output"))
      (node (ref "U1M3") (pin "P$11") (pinfunction "OUT_B_P$11") (pintype "output"))
      (node (ref "U1M3") (pin "P$12") (pinfunction "OUT_B_P$12") (pintype "output"))
      (node (ref "U1M3") (pin "P$13") (pinfunction "OUT_B_P$13") (pintype "output"))
      (node (ref "U1M3") (pin "P$14") (pinfunction "OUT_B_P$14") (pintype "output"))
      (node (ref "U1M3") (pin "P$15") (pinfunction "OUT_B_P$15") (pintype "output"))
      (node (ref "U1M3") (pin "P$16") (pinfunction "OUT_B_P$16") (pintype "output"))
      (node (ref "U1M3") (pin "P$17") (pinfunction "OUT_B_P$17") (pintype "output"))
      (node (ref "U1M3") (pin "P$18") (pinfunction "OUT_B_P$18") (pintype "output"))
      (node (ref "U1M3") (pin "P15") (pinfunction "OUT_B_P15") (pintype "output"))
      (node (ref "U1M3") (pin "P16") (pinfunction "OUT_B_P16") (pintype "output"))
      (node (ref "U1M3") (pin "P21") (pinfunction "OUT_B_P21") (pintype "output"))
      (node (ref "U1M3") (pin "SLUG3") (pinfunction "OUT_B_SLUG3") (pintype "output"))
    )
    (net (code "143") (name "OUTBM4") (class "Default")
      (node (ref "CONN_M4") (pin "-") (pinfunction "P$V-_-") (pintype "bidirectional"))
      (node (ref "R12M4") (pin "2") (pinfunction "2_2") (pintype "passive"))
      (node (ref "U1M4") (pin "P$10") (pinfunction "OUT_B_P$10") (pintype "output"))
      (node (ref "U1M4") (pin "P$11") (pinfunction "OUT_B_P$11") (pintype "output"))
      (node (ref "U1M4") (pin "P$12") (pinfunction "OUT_B_P$12") (pintype "output"))
      (node (ref "U1M4") (pin "P$13") (pinfunction "OUT_B_P$13") (pintype "output"))
      (node (ref "U1M4") (pin "P$14") (pinfunction "OUT_B_P$14") (pintype "output"))
      (node (ref "U1M4") (pin "P$15") (pinfunction "OUT_B_P$15") (pintype "output"))
      (node (ref "U1M4") (pin "P$16") (pinfunction "OUT_B_P$16") (pintype "output"))
      (node (ref "U1M4") (pin "P$17") (pinfunction "OUT_B_P$17") (pintype "output"))
      (node (ref "U1M4") (pin "P$18") (pinfunction "OUT_B_P$18") (pintype "output"))
      (node (ref "U1M4") (pin "P15") (pinfunction "OUT_B_P15") (pintype "output"))
      (node (ref "U1M4") (pin "P16") (pinfunction "OUT_B_P16") (pintype "output"))
      (node (ref "U1M4") (pin "P21") (pinfunction "OUT_B_P21") (pintype "output"))
      (node (ref "U1M4") (pin "SLUG3") (pinfunction "OUT_B_SLUG3") (pintype "output"))
    )
    (net (code "144") (name "PT22") (class "Default")
      (node (ref "1C6") (pin "1") (pinfunction "1_1") (pintype "passive"))
      (node (ref "1PT22") (pin "E") (pinfunction "E1_E") (pintype "passive"))
      (node (ref "1R7") (pin "2") (pinfunction "2_2") (pintype "passive"))
      (node (ref "1U3") (pin "8") (pinfunction "CHAN1_8") (pintype "bidirectional"))
    )
    (net (code "145") (name "PT23") (class "Default")
      (node (ref "1C13") (pin "1") (pinfunction "1_1") (pintype "passive"))
      (node (ref "1PT23") (pin "E") (pinfunction "E1_E") (pintype "passive"))
      (node (ref "1R12") (pin "2") (pinfunction "2_2") (pintype "passive"))
      (node (ref "1U3") (pin "7") (pinfunction "CHAN2_7") (pintype "bidirectional"))
    )
    (net (code "146") (name "PT24") (class "Default")
      (node (ref "1C14") (pin "1") (pinfunction "1_1") (pintype "passive"))
      (node (ref "1PT24") (pin "E") (pinfunction "E1_E") (pintype "passive"))
      (node (ref "1R13") (pin "2") (pinfunction "2_2") (pintype "passive"))
      (node (ref "1U3") (pin "6") (pinfunction "CHAN3_6") (pintype "bidirectional"))
    )
    (net (code "147") (name "PT25") (class "Default")
      (node (ref "1C15") (pin "1") (pinfunction "1_1") (pintype "passive"))
      (node (ref "1PT25") (pin "E") (pinfunction "E1_E") (pintype "passive"))
      (node (ref "1R14") (pin "2") (pinfunction "2_2") (pintype "passive"))
      (node (ref "1U3") (pin "5") (pinfunction "CHAN4_5") (pintype "bidirectional"))
    )
    (net (code "148") (name "PT37") (class "Default")
      (node (ref "1C16") (pin "1") (pinfunction "1_1") (pintype "passive"))
      (node (ref "1PT37") (pin "E") (pinfunction "E1_E") (pintype "passive"))
      (node (ref "1R15") (pin "2") (pinfunction "2_2") (pintype "passive"))
      (node (ref "1U3") (pin "19") (pinfunction "CHAN12_19") (pintype "bidirectional"))
    )
    (net (code "149") (name "PT38") (class "Default")
      (node (ref "1C17") (pin "1") (pinfunction "1_1") (pintype "passive"))
      (node (ref "1PT38") (pin "E") (pinfunction "E1_E") (pintype "passive"))
      (node (ref "1R16") (pin "2") (pinfunction "2_2") (pintype "passive"))
      (node (ref "1U3") (pin "4") (pinfunction "CHAN5_4") (pintype "bidirectional"))
    )
    (net (code "150") (name "PWMM1") (class "Default")
      (node (ref "R11M1") (pin "2") (pinfunction "2_2") (pintype "passive"))
      (node (ref "R7M1") (pin "2") (pinfunction "2_2") (pintype "passive"))
      (node (ref "X1") (pin "7") (pinfunction "7_7") (pintype "passive"))
    )
    (net (code "151") (name "PWMM2") (class "Default")
      (node (ref "R11M2") (pin "2") (pinfunction "2_2") (pintype "passive"))
      (node (ref "R7M2") (pin "2") (pinfunction "2_2") (pintype "passive"))
      (node (ref "X1") (pin "5") (pinfunction "5_5") (pintype "passive"))
    )
    (net (code "152") (name "PWMM3") (class "Default")
      (node (ref "R11M3") (pin "2") (pinfunction "2_2") (pintype "passive"))
      (node (ref "R7M3") (pin "2") (pinfunction "2_2") (pintype "passive"))
      (node (ref "X1") (pin "3") (pinfunction "3_3") (pintype "passive"))
    )
    (net (code "153") (name "PWMM4") (class "Default")
      (node (ref "R11M4") (pin "2") (pinfunction "2_2") (pintype "passive"))
      (node (ref "R7M4") (pin "2") (pinfunction "2_2") (pintype "passive"))
      (node (ref "X1") (pin "1") (pinfunction "1_1") (pintype "passive"))
    )
    (net (code "154") (name "RESET") (class "Default")
      (node (ref "1R9") (pin "1") (pinfunction "1_1") (pintype "passive"))
      (node (ref "1SW1") (pin "P$2") (pinfunction "2_P$2") (pintype "passive"))
      (node (ref "1U4") (pin "7") (pinfunction "NRST_7") (pintype "input"))
    )
    (net (code "155") (name "RX") (class "Default")
      (node (ref "1U4") (pin "31") (pinfunction "PA10/USART1_RX/TIM1_CH3_31") (pintype "bidirectional"))
      (node (ref "X1") (pin "9") (pinfunction "9_9") (pintype "passive"))
    )
    (net (code "156") (name "S0") (class "Default")
      (node (ref "1U1") (pin "10") (pinfunction "S0_10") (pintype "input"))
      (node (ref "1U2") (pin "10") (pinfunction "S0_10") (pintype "input"))
      (node (ref "1U3") (pin "10") (pinfunction "S0_10") (pintype "input"))
      (node (ref "1U4") (pin "38") (pinfunction "PA15/JTDI_38") (pintype "bidirectional"))
    )
    (net (code "157") (name "S1") (class "Default")
      (node (ref "1U1") (pin "11") (pinfunction "S1_11") (pintype "input"))
      (node (ref "1U2") (pin "11") (pinfunction "S1_11") (pintype "input"))
      (node (ref "1U3") (pin "11") (pinfunction "S1_11") (pintype "input"))
      (node (ref "1U4") (pin "39") (pinfunction "PB3/JTDO_39") (pintype "bidirectional"))
    )
    (net (code "158") (name "S2") (class "Default")
      (node (ref "1U1") (pin "14") (pinfunction "S2_14") (pintype "input"))
      (node (ref "1U2") (pin "14") (pinfunction "S2_14") (pintype "input"))
      (node (ref "1U3") (pin "14") (pinfunction "S2_14") (pintype "input"))
      (node (ref "1U4") (pin "40") (pinfunction "PB4/NJTRST_40") (pintype "bidirectional"))
    )
    (net (code "159") (name "S3") (class "Default")
      (node (ref "1U1") (pin "13") (pinfunction "S3_13") (pintype "input"))
      (node (ref "1U2") (pin "13") (pinfunction "S3_13") (pintype "input"))
      (node (ref "1U3") (pin "13") (pinfunction "S3_13") (pintype "input"))
      (node (ref "1U4") (pin "41") (pinfunction "PB5/I2C1_SMBA_41") (pintype "input"))
    )
    (net (code "160") (name "SOLENOIDON") (class "Default")
      (node (ref "1U4") (pin "29") (pinfunction "PA8/USART1_CK/TIM1_CH1/MCO_29") (pintype "bidirectional"))
      (node (ref "3Q4") (pin "1") (pinfunction "G_1") (pintype "bidirectional"))
      (node (ref "3R9") (pin "2") (pinfunction "2_2") (pintype "passive"))
    )
    (net (code "161") (name "SWDCLK") (class "Default")
      (node (ref "1U4") (pin "37") (pinfunction "PA14/JTCK/SWCLK_37") (pintype "bidirectional"))
      (node (ref "SWD") (pin "2") (pinfunction "2_2") (pintype "passive"))
    )
    (net (code "162") (name "SWDIO") (class "Default")
      (node (ref "1U4") (pin "34") (pinfunction "PA13/JTMS/SWDIO_34") (pintype "bidirectional"))
      (node (ref "SWD") (pin "3") (pinfunction "3_3") (pintype "passive"))
    )
    (net (code "163") (name "THERM1") (class "Default")
      (node (ref "1U3") (pin "18") (pinfunction "CHAN13_18") (pintype "bidirectional"))
      (node (ref "R5") (pin "2") (pinfunction "2_2") (pintype "passive"))
      (node (ref "THERM1") (pin "2") (pinfunction "2_2") (pintype "passive"))
    )
    (net (code "164") (name "THERM2") (class "Default")
      (node (ref "1U3") (pin "16") (pinfunction "CHAN15_16") (pintype "bidirectional"))
      (node (ref "R6") (pin "2") (pinfunction "2_2") (pintype "passive"))
      (node (ref "THERM2") (pin "2") (pinfunction "2_2") (pintype "passive"))
    )
    (net (code "165") (name "THERM3") (class "Default")
      (node (ref "1U3") (pin "23") (pinfunction "CHAN8_23") (pintype "bidirectional"))
      (node (ref "R7") (pin "2") (pinfunction "2_2") (pintype "passive"))
      (node (ref "THERM3") (pin "2") (pinfunction "2_2") (pintype "passive"))
    )
    (net (code "166") (name "THERM4") (class "Default")
      (node (ref "1U3") (pin "22") (pinfunction "CHAN9_22") (pintype "bidirectional"))
      (node (ref "R8") (pin "2") (pinfunction "2_2") (pintype "passive"))
      (node (ref "THERM4") (pin "2") (pinfunction "2_2") (pintype "passive"))
    )
    (net (code "167") (name "TX") (class "Default")
      (node (ref "1U4") (pin "30") (pinfunction "PA9/USART1_TX/TIM1_CH2_30") (pintype "input"))
      (node (ref "X1") (pin "10") (pinfunction "10_10") (pintype "passive"))
    )
    (net (code "168") (name "VBAT") (class "Default")
      (node (ref "1U4") (pin "1") (pinfunction "VBAT_1") (pintype "power_in"))
    )
    (net (code "169") (name "VCCA") (class "Default")
      (node (ref "1C1") (pin "1") (pinfunction "1_1") (pintype "passive"))
      (node (ref "1C12") (pin "2") (pinfunction "2_2") (pintype "passive"))
      (node (ref "1C3") (pin "1") (pinfunction "1_1") (pintype "passive"))
      (node (ref "1C5") (pin "1") (pinfunction "1_1") (pintype "passive"))
      (node (ref "1PT1") (pin "C") (pinfunction "C1_C") (pintype "passive"))
      (node (ref "1PT10") (pin "C") (pinfunction "C1_C") (pintype "passive"))
      (node (ref "1PT11") (pin "C") (pinfunction "C1_C") (pintype "passive"))
      (node (ref "1PT12") (pin "C") (pinfunction "C1_C") (pintype "passive"))
      (node (ref "1PT13") (pin "C") (pinfunction "C1_C") (pintype "passive"))
      (node (ref "1PT14") (pin "C") (pinfunction "C1_C") (pintype "passive"))
      (node (ref "1PT15") (pin "C") (pinfunction "C1_C") (pintype "passive"))
      (node (ref "1PT16") (pin "C") (pinfunction "C1_C") (pintype "passive"))
      (node (ref "1PT17") (pin "C") (pinfunction "C1_C") (pintype "passive"))
      (node (ref "1PT18") (pin "C") (pinfunction "C1_C") (pintype "passive"))
      (node (ref "1PT19") (pin "C") (pinfunction "C1_C") (pintype "passive"))
      (node (ref "1PT2") (pin "C") (pinfunction "C1_C") (pintype "passive"))
      (node (ref "1PT20") (pin "C") (pinfunction "C1_C") (pintype "passive"))
      (node (ref "1PT21") (pin "C") (pinfunction "C1_C") (pintype "passive"))
      (node (ref "1PT22") (pin "C") (pinfunction "C1_C") (pintype "passive"))
      (node (ref "1PT23") (pin "C") (pinfunction "C1_C") (pintype "passive"))
      (node (ref "1PT24") (pin "C") (pinfunction "C1_C") (pintype "passive"))
      (node (ref "1PT25") (pin "C") (pinfunction "C1_C") (pintype "passive"))
      (node (ref "1PT26") (pin "C") (pinfunction "C1_C") (pintype "passive"))
      (node (ref "1PT27") (pin "C") (pinfunction "C1_C") (pintype "passive"))
      (node (ref "1PT28") (pin "C") (pinfunction "C1_C") (pintype "passive"))
      (node (ref "1PT29") (pin "C") (pinfunction "C1_C") (pintype "passive"))
      (node (ref "1PT3") (pin "C") (pinfunction "C1_C") (pintype "passive"))
      (node (ref "1PT30") (pin "C") (pinfunction "C1_C") (pintype "passive"))
      (node (ref "1PT31") (pin "C") (pinfunction "C1_C") (pintype "passive"))
      (node (ref "1PT32") (pin "C") (pinfunction "C1_C") (pintype "passive"))
      (node (ref "1PT33") (pin "C") (pinfunction "C1_C") (pintype "passive"))
      (node (ref "1PT34") (pin "C") (pinfunction "C1_C") (pintype "passive"))
      (node (ref "1PT35") (pin "C") (pinfunction "C1_C") (pintype "passive"))
      (node (ref "1PT36") (pin "C") (pinfunction "C1_C") (pintype "passive"))
      (node (ref "1PT37") (pin "C") (pinfunction "C1_C") (pintype "passive"))
      (node (ref "1PT38") (pin "C") (pinfunction "C1_C") (pintype "passive"))
      (node (ref "1PT4") (pin "C") (pinfunction "C1_C") (pintype "passive"))
      (node (ref "1PT5") (pin "C") (pinfunction "C1_C") (pintype "passive"))
      (node (ref "1PT6") (pin "C") (pinfunction "C1_C") (pintype "passive"))
      (node (ref "1PT7") (pin "C") (pinfunction "C1_C") (pintype "passive"))
      (node (ref "1PT8") (pin "C") (pinfunction "C1_C") (pintype "passive"))
      (node (ref "1PT9") (pin "C") (pinfunction "C1_C") (pintype "passive"))
      (node (ref "1U1") (pin "24") (pinfunction "VCC_24") (pintype "bidirectional"))
      (node (ref "1U2") (pin "24") (pinfunction "VCC_24") (pintype "bidirectional"))
      (node (ref "1U3") (pin "24") (pinfunction "VCC_24") (pintype "bidirectional"))
      (node (ref "1U4") (pin "9") (pinfunction "VDD_A_9") (pintype "power_in"))
      (node (ref "FB2") (pin "1") (pinfunction "1_1") (pintype "passive"))
      (node (ref "GATE1") (pin "1") (pinfunction "1_1") (pintype "passive"))
      (node (ref "GATE2") (pin "1") (pinfunction "1_1") (pintype "passive"))
      (node (ref "THERM1") (pin "1") (pinfunction "1_1") (pintype "passive"))
      (node (ref "THERM2") (pin "1") (pinfunction "1_1") (pintype "passive"))
      (node (ref "THERM3") (pin "1") (pinfunction "1_1") (pintype "passive"))
      (node (ref "THERM4") (pin "1") (pinfunction "1_1") (pintype "passive"))
      (node (ref "U$19") (pin "P$1") (pinfunction "1_P$1") (pintype "passive"))
      (node (ref "U$24") (pin "P$1") (pinfunction "1_P$1") (pintype "passive"))
    )
    (net (code "170") (name "VCC_1") (class "Default")
      (node (ref "3C1") (pin "+") (pinfunction "+_+") (pintype "passive"))
      (node (ref "3L1") (pin "1") (pinfunction "1_1") (pintype "passive"))
      (node (ref "3R7") (pin "1") (pinfunction "1_1") (pintype "passive"))
      (node (ref "3R8") (pin "2") (pinfunction "2_2") (pintype "passive"))
      (node (ref "3U1") (pin "P5") (pinfunction "VIN_P5") (pintype "power_in"))
      (node (ref "U$16") (pin "P$1") (pinfunction "1_P$1") (pintype "passive"))
    )
    (net (code "171") (name "VCC_2") (class "Default")
      (node (ref "3C3") (pin "+") (pinfunction "+_+") (pintype "passive"))
      (node (ref "3C4") (pin "+") (pinfunction "+_+") (pintype "passive"))
      (node (ref "3D1") (pin "C") (pinfunction "C_C") (pintype "passive"))
      (node (ref "3D4") (pin "A") (pinfunction "A_A") (pintype "passive"))
      (node (ref "3R4") (pin "2") (pinfunction "2_2") (pintype "passive"))
      (node (ref "J1") (pin "+") (pinfunction "P$V+_+") (pintype "bidirectional"))
    )
    (net (code "172") (name "unconnected-(1U4-PA12{slash}USART1_RTS{slash}CAN_TX{slash}TIM1_ETR{slash}USBDP-Pad33)") (class "Default")
      (node (ref "1U4") (pin "33") (pinfunction "PA12/USART1_RTS/CAN_TX/TIM1_ETR/USBDP_33") (pintype "bidirectional"))
    )
    (net (code "173") (name "unconnected-(1U4-PB2{slash}BOOT1-Pad20)") (class "Default")
      (node (ref "1U4") (pin "20") (pinfunction "PB2/BOOT1_20") (pintype "bidirectional"))
    )
    (net (code "174") (name "unconnected-(1U4-PB6{slash}I2C1_SCL{slash}TIM4_CH1-Pad42)") (class "Default")
      (node (ref "1U4") (pin "42") (pinfunction "PB6/I2C1_SCL/TIM4_CH1_42") (pintype "input"))
    )
    (net (code "175") (name "unconnected-(1U4-PB7{slash}I2C1_SDA{slash}TIM4_CH2-Pad43)") (class "Default")
      (node (ref "1U4") (pin "43") (pinfunction "PB7/I2C1_SDA/TIM4_CH2_43") (pintype "bidirectional"))
    )
    (net (code "176") (name "unconnected-(1U4-PB10{slash}I2C2_SCL{slash}USART3_TX-Pad21)") (class "Default")
      (node (ref "1U4") (pin "21") (pinfunction "PB10/I2C2_SCL/USART3_TX_21") (pintype "input"))
    )
    (net (code "177") (name "unconnected-(1U4-PB11{slash}I2C2_SDA{slash}USART3_RX-Pad22)") (class "Default")
      (node (ref "1U4") (pin "22") (pinfunction "PB11/I2C2_SDA/USART3_RX_22") (pintype "input"))
    )
    (net (code "178") (name "unconnected-(1U4-PB12{slash}SPI2_NSS{slash}I2C2_SMBA{slash}USART3_CK{slash}TIM1_BKIN-Pad25)") (class "Default")
      (node (ref "1U4") (pin "25") (pinfunction "PB12/SPI2_NSS/I2C2_SMBA/USART3_CK/TIM1_BKIN_25") (pintype "input"))
    )
    (net (code "179") (name "unconnected-(1U4-PB13{slash}SPI2_SCK{slash}USART3_CTS{slash}TIM1_CH1N-Pad26)") (class "Default")
      (node (ref "1U4") (pin "26") (pinfunction "PB13/SPI2_SCK/USART3_CTS/TIM1_CH1N_26") (pintype "input"))
    )
    (net (code "180") (name "unconnected-(1U4-PB14{slash}SPI2_MISO{slash}USART3_RTS{slash}TIM1_CH2N-Pad27)") (class "Default")
      (node (ref "1U4") (pin "27") (pinfunction "PB14/SPI2_MISO/USART3_RTS/TIM1_CH2N_27") (pintype "input"))
    )
    (net (code "181") (name "unconnected-(1U4-PB15{slash}SPI2_MOSI{slash}TIM1_CH3N-Pad28)") (class "Default")
      (node (ref "1U4") (pin "28") (pinfunction "PB15/SPI2_MOSI/TIM1_CH3N_28") (pintype "input"))
    )
    (net (code "182") (name "unconnected-(1U4-PC14-OSC32_IN-Pad3)") (class "Default")
      (node (ref "1U4") (pin "3") (pinfunction "PC14-OSC32_IN_3") (pintype "input"))
    )
    (net (code "183") (name "unconnected-(1U4-PC15-OSC32_OUT-Pad4)") (class "Default")
      (node (ref "1U4") (pin "4") (pinfunction "PC15-OSC32_OUT_4") (pintype "input"))
    )
    (net (code "184") (name "unconnected-(2U1-ENA-Pad5)") (class "Default")
      (node (ref "2U1") (pin "5") (pinfunction "ENA_5") (pintype "input"))
    )
    (net (code "185") (name "unconnected-(2U1-NC-Pad2)") (class "Default")
      (node (ref "2U1") (pin "2") (pinfunction "NC_2") (pintype "no_connect"))
    )
    (net (code "186") (name "unconnected-(2U1-NC-Pad3)") (class "Default")
      (node (ref "2U1") (pin "3") (pinfunction "NC_3") (pintype "no_connect"))
    )
    (net (code "187") (name "unconnected-(U$30-O-Pad1)") (class "Default")
      (node (ref "U$30") (pin "1") (pinfunction "O_1") (pintype "passive"))
    )
    (net (code "188") (name "unconnected-(U1M1-NC-PadP2)") (class "Default")
      (node (ref "U1M1") (pin "P2") (pinfunction "NC_P2") (pintype "no_connect"))
    )
    (net (code "189") (name "unconnected-(U1M1-NC-PadP14)") (class "Default")
      (node (ref "U1M1") (pin "P14") (pinfunction "NC_P14") (pintype "no_connect"))
    )
    (net (code "190") (name "unconnected-(U1M1-NC-PadP17)") (class "Default")
      (node (ref "U1M1") (pin "P17") (pinfunction "NC_P17") (pintype "no_connect"))
    )
    (net (code "191") (name "unconnected-(U1M1-NC-PadP22)") (class "Default")
      (node (ref "U1M1") (pin "P22") (pinfunction "NC_P22") (pintype "no_connect"))
    )
    (net (code "192") (name "unconnected-(U1M1-NC-PadP24)") (class "Default")
      (node (ref "U1M1") (pin "P24") (pinfunction "NC_P24") (pintype "no_connect"))
    )
    (net (code "193") (name "unconnected-(U1M1-NC-PadP29)") (class "Default")
      (node (ref "U1M1") (pin "P29") (pinfunction "NC_P29") (pintype "no_connect"))
    )
    (net (code "194") (name "unconnected-(U1M2-NC-PadP2)") (class "Default")
      (node (ref "U1M2") (pin "P2") (pinfunction "NC_P2") (pintype "no_connect"))
    )
    (net (code "195") (name "unconnected-(U1M2-NC-PadP14)") (class "Default")
      (node (ref "U1M2") (pin "P14") (pinfunction "NC_P14") (pintype "no_connect"))
    )
    (net (code "196") (name "unconnected-(U1M2-NC-PadP17)") (class "Default")
      (node (ref "U1M2") (pin "P17") (pinfunction "NC_P17") (pintype "no_connect"))
    )
    (net (code "197") (name "unconnected-(U1M2-NC-PadP22)") (class "Default")
      (node (ref "U1M2") (pin "P22") (pinfunction "NC_P22") (pintype "no_connect"))
    )
    (net (code "198") (name "unconnected-(U1M2-NC-PadP24)") (class "Default")
      (node (ref "U1M2") (pin "P24") (pinfunction "NC_P24") (pintype "no_connect"))
    )
    (net (code "199") (name "unconnected-(U1M2-NC-PadP29)") (class "Default")
      (node (ref "U1M2") (pin "P29") (pinfunction "NC_P29") (pintype "no_connect"))
    )
    (net (code "200") (name "unconnected-(U1M3-NC-PadP2)") (class "Default")
      (node (ref "U1M3") (pin "P2") (pinfunction "NC_P2") (pintype "no_connect"))
    )
    (net (code "201") (name "unconnected-(U1M3-NC-PadP14)") (class "Default")
      (node (ref "U1M3") (pin "P14") (pinfunction "NC_P14") (pintype "no_connect"))
    )
    (net (code "202") (name "unconnected-(U1M3-NC-PadP17)") (class "Default")
      (node (ref "U1M3") (pin "P17") (pinfunction "NC_P17") (pintype "no_connect"))
    )
    (net (code "203") (name "unconnected-(U1M3-NC-PadP22)") (class "Default")
      (node (ref "U1M3") (pin "P22") (pinfunction "NC_P22") (pintype "no_connect"))
    )
    (net (code "204") (name "unconnected-(U1M3-NC-PadP24)") (class "Default")
      (node (ref "U1M3") (pin "P24") (pinfunction "NC_P24") (pintype "no_connect"))
    )
    (net (code "205") (name "unconnected-(U1M3-NC-PadP29)") (class "Default")
      (node (ref "U1M3") (pin "P29") (pinfunction "NC_P29") (pintype "no_connect"))
    )
    (net (code "206") (name "unconnected-(U1M4-NC-PadP2)") (class "Default")
      (node (ref "U1M4") (pin "P2") (pinfunction "NC_P2") (pintype "no_connect"))
    )
    (net (code "207") (name "unconnected-(U1M4-NC-PadP14)") (class "Default")
      (node (ref "U1M4") (pin "P14") (pinfunction "NC_P14") (pintype "no_connect"))
    )
    (net (code "208") (name "unconnected-(U1M4-NC-PadP17)") (class "Default")
      (node (ref "U1M4") (pin "P17") (pinfunction "NC_P17") (pintype "no_connect"))
    )
    (net (code "209") (name "unconnected-(U1M4-NC-PadP22)") (class "Default")
      (node (ref "U1M4") (pin "P22") (pinfunction "NC_P22") (pintype "no_connect"))
    )
    (net (code "210") (name "unconnected-(U1M4-NC-PadP24)") (class "Default")
      (node (ref "U1M4") (pin "P24") (pinfunction "NC_P24") (pintype "no_connect"))
    )
    (net (code "211") (name "unconnected-(U1M4-NC-PadP29)") (class "Default")
      (node (ref "U1M4") (pin "P29") (pinfunction "NC_P29") (pintype "no_connect"))
    )
  )
)
